# ATEMconsole.net
KiCad netlist of a schematic drawn in EAGLE
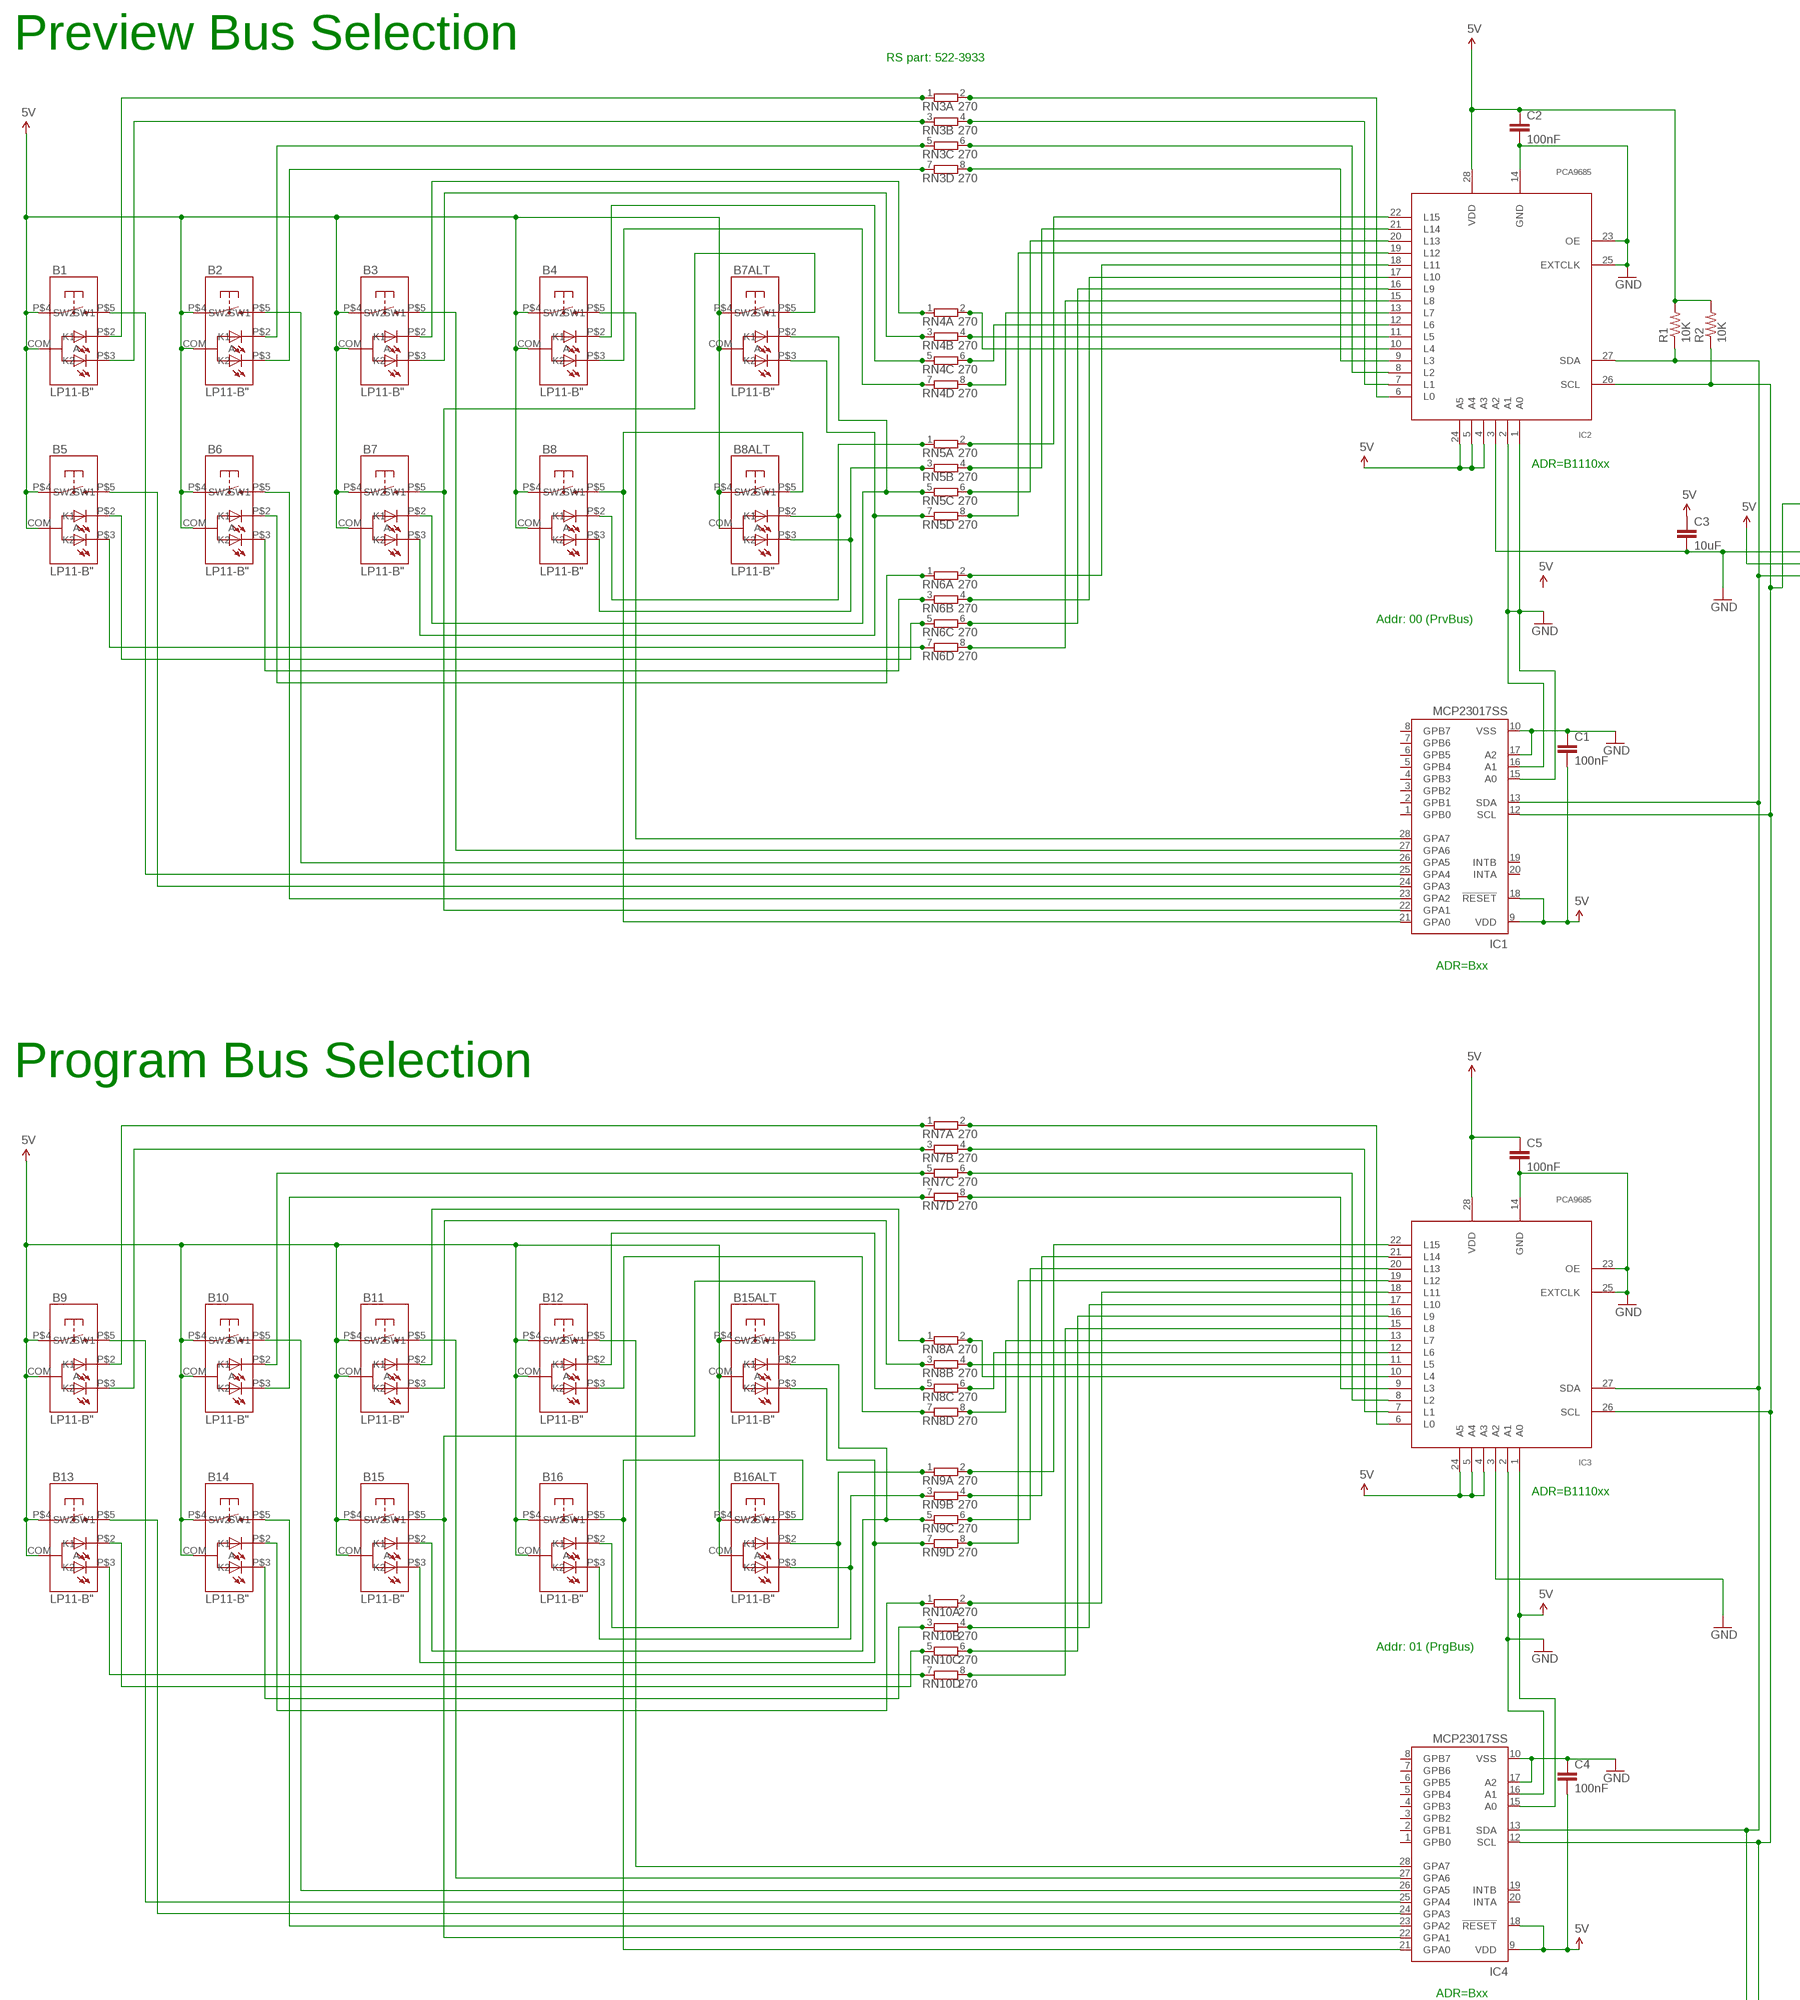
[diagram p0: schematic, sheet 1, part 1 of 3]
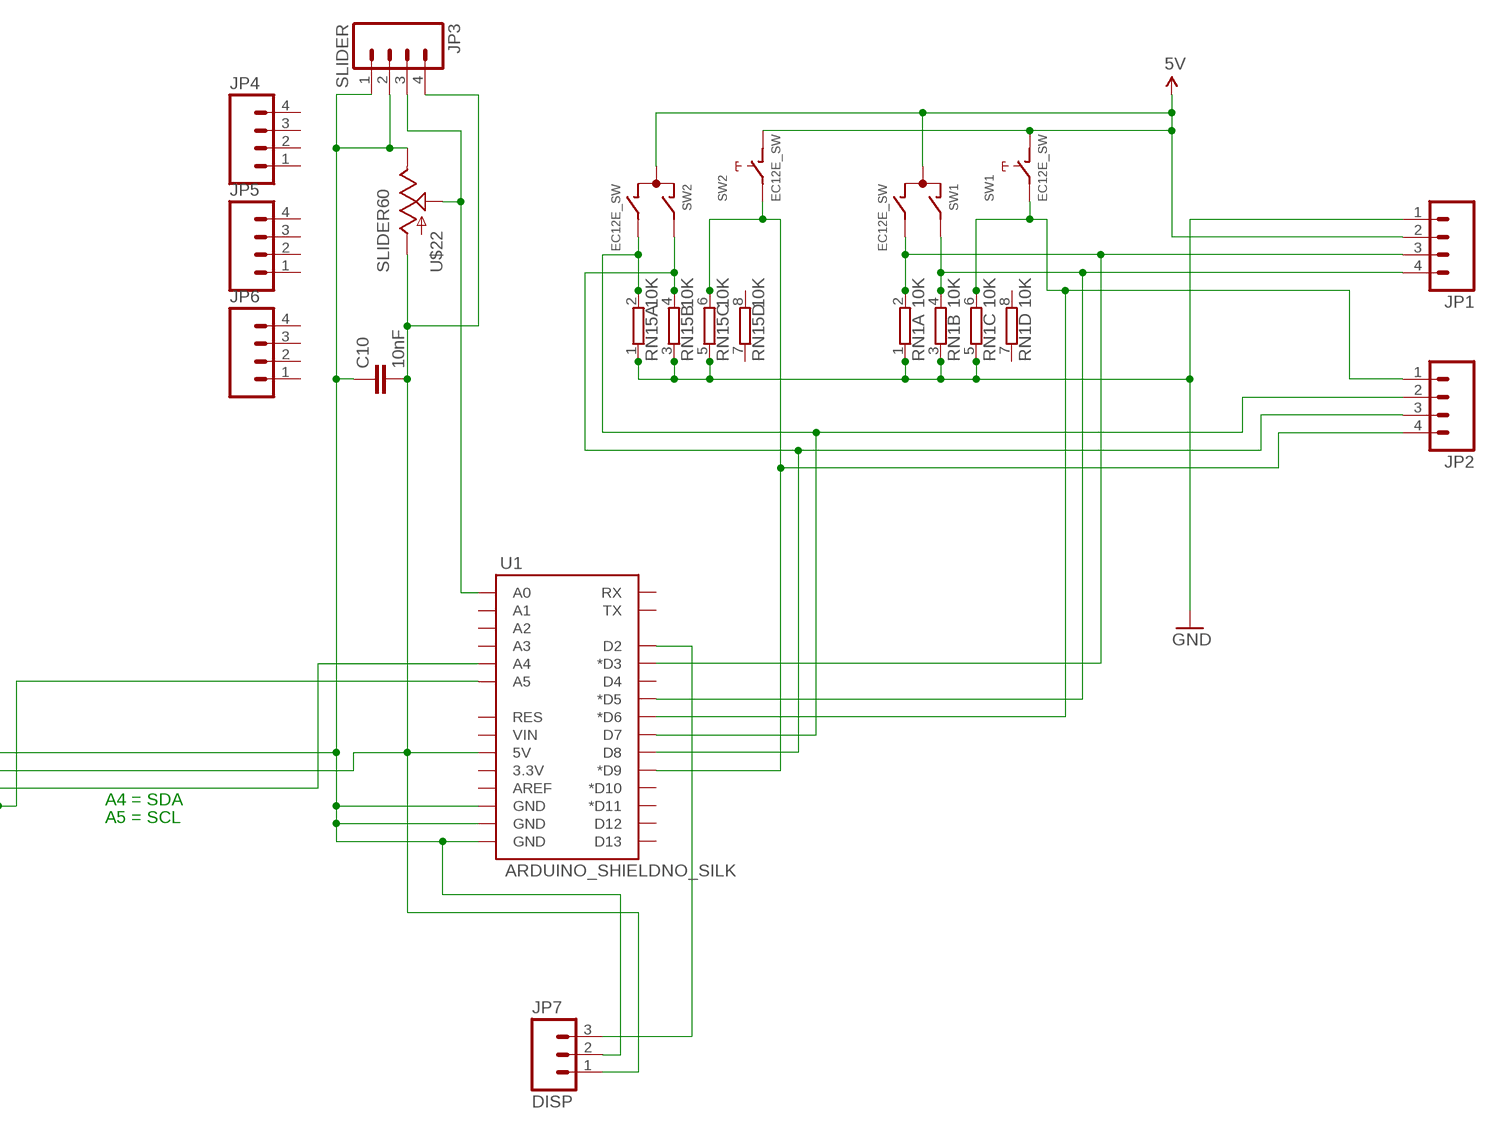
[diagram p1: schematic, sheet 1, part 2 of 3]
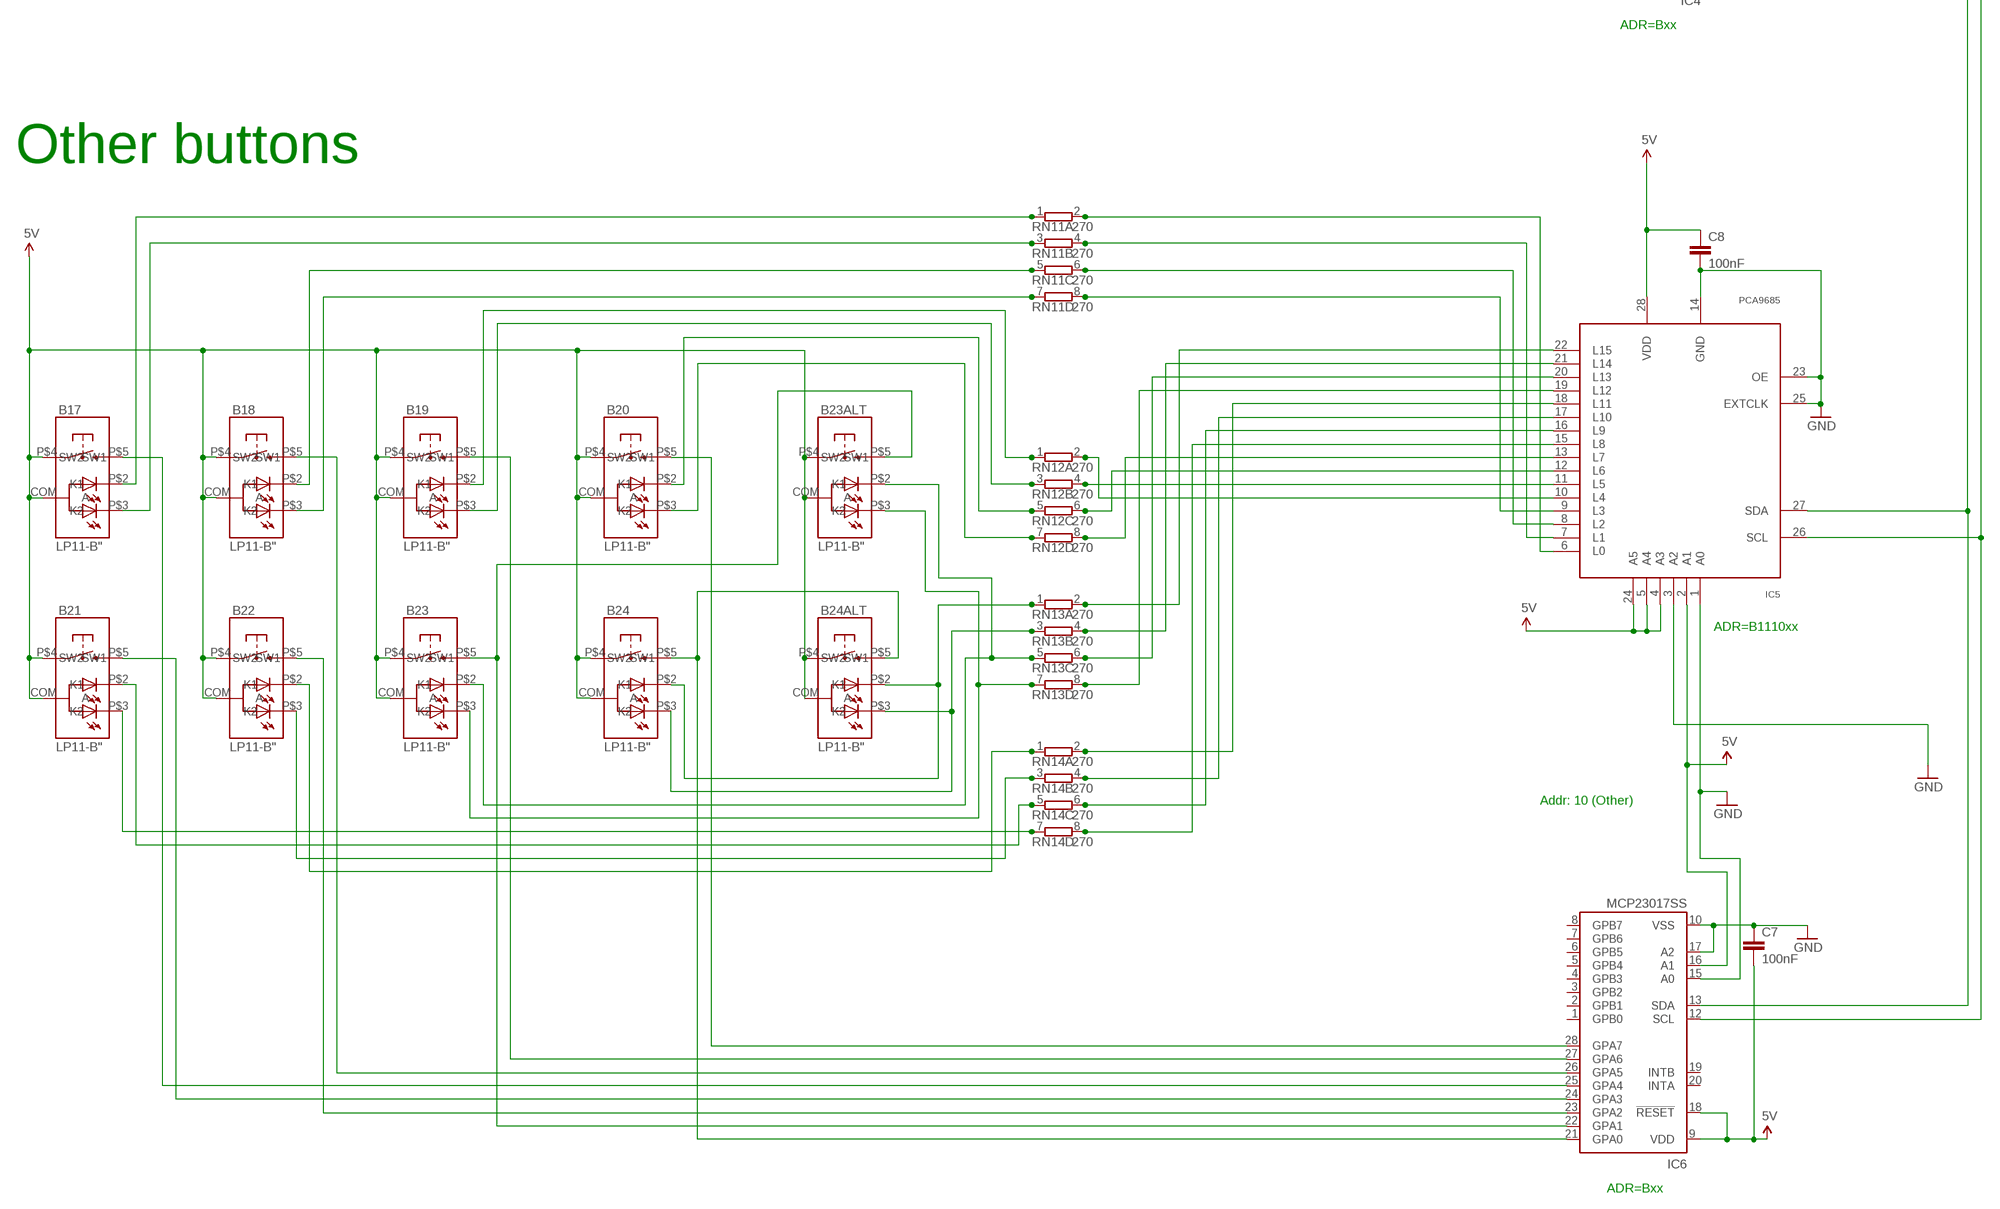
[diagram p2: schematic, sheet 1, part 3 of 3]

(export (version "E")
  (design (tool "Eeschema 10.0.6"))
  (components
    (comp (ref "B1")
      (value "LP11-B\"")
      (footprint "eagle-import:LP11")
      (libsource (lib "eagle-import") (part "LP11-B{dblquote}"))
    )
    (comp (ref "B2")
      (value "LP11-B\"")
      (footprint "eagle-import:LP11")
      (libsource (lib "eagle-import") (part "LP11-B{dblquote}"))
    )
    (comp (ref "B3")
      (value "LP11-B\"")
      (footprint "eagle-import:LP11")
      (libsource (lib "eagle-import") (part "LP11-B{dblquote}"))
    )
    (comp (ref "B4")
      (value "LP11-B\"")
      (footprint "eagle-import:LP11")
      (libsource (lib "eagle-import") (part "LP11-B{dblquote}"))
    )
    (comp (ref "B5")
      (value "LP11-B\"")
      (footprint "eagle-import:LP11")
      (libsource (lib "eagle-import") (part "LP11-B{dblquote}"))
    )
    (comp (ref "B6")
      (value "LP11-B\"")
      (footprint "eagle-import:LP11")
      (libsource (lib "eagle-import") (part "LP11-B{dblquote}"))
    )
    (comp (ref "B7")
      (value "LP11-B\"")
      (footprint "eagle-import:LP11")
      (libsource (lib "eagle-import") (part "LP11-B{dblquote}"))
    )
    (comp (ref "B7ALT")
      (value "LP11-B\"")
      (footprint "eagle-import:LP11")
      (libsource (lib "eagle-import") (part "LP11-B{dblquote}"))
    )
    (comp (ref "B8")
      (value "LP11-B\"")
      (footprint "eagle-import:LP11")
      (libsource (lib "eagle-import") (part "LP11-B{dblquote}"))
    )
    (comp (ref "B8ALT")
      (value "LP11-B\"")
      (footprint "eagle-import:LP11")
      (libsource (lib "eagle-import") (part "LP11-B{dblquote}"))
    )
    (comp (ref "B9")
      (value "LP11-B\"")
      (footprint "eagle-import:LP11")
      (libsource (lib "eagle-import") (part "LP11-B{dblquote}"))
    )
    (comp (ref "B10")
      (value "LP11-B\"")
      (footprint "eagle-import:LP11")
      (libsource (lib "eagle-import") (part "LP11-B{dblquote}"))
    )
    (comp (ref "B11")
      (value "LP11-B\"")
      (footprint "eagle-import:LP11")
      (libsource (lib "eagle-import") (part "LP11-B{dblquote}"))
    )
    (comp (ref "B12")
      (value "LP11-B\"")
      (footprint "eagle-import:LP11")
      (libsource (lib "eagle-import") (part "LP11-B{dblquote}"))
    )
    (comp (ref "B13")
      (value "LP11-B\"")
      (footprint "eagle-import:LP11")
      (libsource (lib "eagle-import") (part "LP11-B{dblquote}"))
    )
    (comp (ref "B14")
      (value "LP11-B\"")
      (footprint "eagle-import:LP11")
      (libsource (lib "eagle-import") (part "LP11-B{dblquote}"))
    )
    (comp (ref "B15")
      (value "LP11-B\"")
      (footprint "eagle-import:LP11")
      (libsource (lib "eagle-import") (part "LP11-B{dblquote}"))
    )
    (comp (ref "B15ALT")
      (value "LP11-B\"")
      (footprint "eagle-import:LP11")
      (libsource (lib "eagle-import") (part "LP11-B{dblquote}"))
    )
    (comp (ref "B16")
      (value "LP11-B\"")
      (footprint "eagle-import:LP11")
      (libsource (lib "eagle-import") (part "LP11-B{dblquote}"))
    )
    (comp (ref "B16ALT")
      (value "LP11-B\"")
      (footprint "eagle-import:LP11")
      (libsource (lib "eagle-import") (part "LP11-B{dblquote}"))
    )
    (comp (ref "B17")
      (value "LP11-B\"")
      (footprint "eagle-import:LP11")
      (libsource (lib "eagle-import") (part "LP11-B{dblquote}"))
    )
    (comp (ref "B18")
      (value "LP11-B\"")
      (footprint "eagle-import:LP11")
      (libsource (lib "eagle-import") (part "LP11-B{dblquote}"))
    )
    (comp (ref "B19")
      (value "LP11-B\"")
      (footprint "eagle-import:LP11")
      (libsource (lib "eagle-import") (part "LP11-B{dblquote}"))
    )
    (comp (ref "B20")
      (value "LP11-B\"")
      (footprint "eagle-import:LP11")
      (libsource (lib "eagle-import") (part "LP11-B{dblquote}"))
    )
    (comp (ref "B21")
      (value "LP11-B\"")
      (footprint "eagle-import:LP11")
      (libsource (lib "eagle-import") (part "LP11-B{dblquote}"))
    )
    (comp (ref "B22")
      (value "LP11-B\"")
      (footprint "eagle-import:LP11")
      (libsource (lib "eagle-import") (part "LP11-B{dblquote}"))
    )
    (comp (ref "B23")
      (value "LP11-B\"")
      (footprint "eagle-import:LP11")
      (libsource (lib "eagle-import") (part "LP11-B{dblquote}"))
    )
    (comp (ref "B23ALT")
      (value "LP11-B\"")
      (footprint "eagle-import:LP11")
      (libsource (lib "eagle-import") (part "LP11-B{dblquote}"))
    )
    (comp (ref "B24")
      (value "LP11-B\"")
      (footprint "eagle-import:LP11")
      (libsource (lib "eagle-import") (part "LP11-B{dblquote}"))
    )
    (comp (ref "B24ALT")
      (value "LP11-B\"")
      (footprint "eagle-import:LP11")
      (libsource (lib "eagle-import") (part "LP11-B{dblquote}"))
    )
    (comp (ref "C1")
      (value "100nF")
      (footprint "eagle-import:AXIAL-5MM")
      (libsource (lib "eagle-import") (part "CAP_"))
    )
    (comp (ref "C2")
      (value "100nF")
      (footprint "eagle-import:AXIAL-5MM")
      (libsource (lib "eagle-import") (part "CAP_"))
    )
    (comp (ref "C3")
      (value "10uF")
      (footprint "eagle-import:AXIAL-5MM")
      (libsource (lib "eagle-import") (part "CAP_"))
    )
    (comp (ref "C4")
      (value "100nF")
      (footprint "eagle-import:AXIAL-5MM")
      (libsource (lib "eagle-import") (part "CAP_"))
    )
    (comp (ref "C5")
      (value "100nF")
      (footprint "eagle-import:AXIAL-5MM")
      (libsource (lib "eagle-import") (part "CAP_"))
    )
    (comp (ref "C7")
      (value "100nF")
      (footprint "eagle-import:AXIAL-5MM")
      (libsource (lib "eagle-import") (part "CAP_"))
    )
    (comp (ref "C8")
      (value "100nF")
      (footprint "eagle-import:AXIAL-5MM")
      (libsource (lib "eagle-import") (part "CAP_"))
    )
    (comp (ref "C10")
      (value "10nF")
      (footprint "eagle-import:AXIAL-5MM")
      (libsource (lib "eagle-import") (part "CAP_"))
    )
    (comp (ref "IC1")
      (value "MCP23017SS")
      (footprint "eagle-import:SSOP28")
      (fields
        (field (name "MF") "MICROCHIP")
        (field (name "MPN") "MCP23017-E/SS")
        (field (name "MPN_1") "MCP23017-E/SS")
        (field (name "OC_FARNELL") "1467674")
        (field (name "OC_NEWARK") "31K2960")
      )
      (libsource (lib "eagle-import") (part "MCP23017SS"))
    )
    (comp (ref "IC2")
      (value "PCA9685")
      (footprint "eagle-import:TSSOP28")
      (libsource (lib "eagle-import") (part "PCA9685"))
    )
    (comp (ref "IC3")
      (value "PCA9685")
      (footprint "eagle-import:TSSOP28")
      (libsource (lib "eagle-import") (part "PCA9685"))
    )
    (comp (ref "IC4")
      (value "MCP23017SS")
      (footprint "eagle-import:SSOP28")
      (fields
        (field (name "MF") "MICROCHIP")
        (field (name "MPN") "MCP23017-E/SS")
        (field (name "MPN_1") "MCP23017-E/SS")
        (field (name "OC_FARNELL") "1467674")
        (field (name "OC_NEWARK") "31K2960")
      )
      (libsource (lib "eagle-import") (part "MCP23017SS"))
    )
    (comp (ref "IC5")
      (value "PCA9685")
      (footprint "eagle-import:TSSOP28")
      (libsource (lib "eagle-import") (part "PCA9685"))
    )
    (comp (ref "IC6")
      (value "MCP23017SS")
      (footprint "eagle-import:SSOP28")
      (fields
        (field (name "MF") "MICROCHIP")
        (field (name "MPN") "MCP23017-E/SS")
        (field (name "MPN_1") "MCP23017-E/SS")
        (field (name "OC_FARNELL") "1467674")
        (field (name "OC_NEWARK") "31K2960")
      )
      (libsource (lib "eagle-import") (part "MCP23017SS"))
    )
    (comp (ref "JP1")
      (value "M04PTH")
      (footprint "eagle-import:1X04")
      (libsource (lib "eagle-import") (part "M04PTH"))
    )
    (comp (ref "JP2")
      (value "M04PTH")
      (footprint "eagle-import:1X04")
      (libsource (lib "eagle-import") (part "M04PTH"))
    )
    (comp (ref "JP3")
      (value "SLIDER")
      (footprint "eagle-import:1X04")
      (libsource (lib "eagle-import") (part "M04PTH"))
    )
    (comp (ref "JP4")
      (value "M04PTH")
      (footprint "eagle-import:1X04")
      (libsource (lib "eagle-import") (part "M04PTH"))
    )
    (comp (ref "JP5")
      (value "M04PTH")
      (footprint "eagle-import:1X04")
      (libsource (lib "eagle-import") (part "M04PTH"))
    )
    (comp (ref "JP6")
      (value "M04PTH")
      (footprint "eagle-import:1X04")
      (libsource (lib "eagle-import") (part "M04PTH"))
    )
    (comp (ref "JP7")
      (value "DISP")
      (footprint "eagle-import:1X03")
      (libsource (lib "eagle-import") (part "M03PTH"))
    )
    (comp (ref "R1")
      (value "10K")
      (footprint "eagle-import:0603-RES")
      (libsource (lib "eagle-import") (part "RESISTOR0603-RES"))
    )
    (comp (ref "R2")
      (value "10K")
      (footprint "eagle-import:0603-RES")
      (libsource (lib "eagle-import") (part "RESISTOR0603-RES"))
    )
    (comp (ref "RN1")
      (value "10K")
      (footprint "eagle-import:SIL8")
      (libsource (lib "eagle-import") (part "E4R"))
    )
    (comp (ref "RN3")
      (value "270")
      (footprint "eagle-import:SIL8")
      (libsource (lib "eagle-import") (part "E4R"))
    )
    (comp (ref "RN4")
      (value "270")
      (footprint "eagle-import:SIL8")
      (libsource (lib "eagle-import") (part "E4R"))
    )
    (comp (ref "RN5")
      (value "270")
      (footprint "eagle-import:SIL8")
      (libsource (lib "eagle-import") (part "E4R"))
    )
    (comp (ref "RN6")
      (value "270")
      (footprint "eagle-import:SIL8")
      (libsource (lib "eagle-import") (part "E4R"))
    )
    (comp (ref "RN7")
      (value "270")
      (footprint "eagle-import:SIL8")
      (libsource (lib "eagle-import") (part "E4R"))
    )
    (comp (ref "RN8")
      (value "270")
      (footprint "eagle-import:SIL8")
      (libsource (lib "eagle-import") (part "E4R"))
    )
    (comp (ref "RN9")
      (value "270")
      (footprint "eagle-import:SIL8")
      (libsource (lib "eagle-import") (part "E4R"))
    )
    (comp (ref "RN10")
      (value "270")
      (footprint "eagle-import:SIL8")
      (libsource (lib "eagle-import") (part "E4R"))
    )
    (comp (ref "RN11")
      (value "270")
      (footprint "eagle-import:SIL8")
      (libsource (lib "eagle-import") (part "E4R"))
    )
    (comp (ref "RN12")
      (value "270")
      (footprint "eagle-import:SIL8")
      (libsource (lib "eagle-import") (part "E4R"))
    )
    (comp (ref "RN13")
      (value "270")
      (footprint "eagle-import:SIL8")
      (libsource (lib "eagle-import") (part "E4R"))
    )
    (comp (ref "RN14")
      (value "270")
      (footprint "eagle-import:SIL8")
      (libsource (lib "eagle-import") (part "E4R"))
    )
    (comp (ref "RN15")
      (value "10K")
      (footprint "eagle-import:SIL8")
      (libsource (lib "eagle-import") (part "E4R"))
    )
    (comp (ref "SW1")
      (value "EC12E_SW")
      (footprint "eagle-import:ALPS_EC12E_SW")
      (fields (field (name "MPN") "EC12E2424407"))
      (libsource (lib "eagle-import") (part "EC12E_SW"))
    )
    (comp (ref "SW2")
      (value "EC12E_SW")
      (footprint "eagle-import:ALPS_EC12E_SW")
      (fields (field (name "MPN") "EC12E2424407"))
      (libsource (lib "eagle-import") (part "EC12E_SW"))
    )
    (comp (ref "U$22")
      (value "SLIDER60")
      (footprint "eagle-import:SLIDER60")
      (libsource (lib "eagle-import") (part "SLIDER60"))
    )
    (comp (ref "U1")
      (value "ARDUINO_SHIELDNO_SILK")
      (footprint "eagle-import:DUEMILANOVE_VIAS")
      (libsource (lib "eagle-import") (part "ARDUINO_SHIELDNO_SILK"))
    )
  )
  (nets
    (net (code "1") (name "5V") (class "Default")
      (node (ref "B1") (pin "COM") (pinfunction "A_COM") (pintype "bidirectional"))
      (node (ref "B1") (pin "P$4") (pinfunction "SW1_P$4") (pintype "bidirectional"))
      (node (ref "B10") (pin "COM") (pinfunction "A_COM") (pintype "bidirectional"))
      (node (ref "B10") (pin "P$4") (pinfunction "SW1_P$4") (pintype "bidirectional"))
      (node (ref "B11") (pin "COM") (pinfunction "A_COM") (pintype "bidirectional"))
      (node (ref "B11") (pin "P$4") (pinfunction "SW1_P$4") (pintype "bidirectional"))
      (node (ref "B12") (pin "COM") (pinfunction "A_COM") (pintype "bidirectional"))
      (node (ref "B12") (pin "P$4") (pinfunction "SW1_P$4") (pintype "bidirectional"))
      (node (ref "B13") (pin "COM") (pinfunction "A_COM") (pintype "bidirectional"))
      (node (ref "B13") (pin "P$4") (pinfunction "SW1_P$4") (pintype "bidirectional"))
      (node (ref "B14") (pin "COM") (pinfunction "A_COM") (pintype "bidirectional"))
      (node (ref "B14") (pin "P$4") (pinfunction "SW1_P$4") (pintype "bidirectional"))
      (node (ref "B15") (pin "COM") (pinfunction "A_COM") (pintype "bidirectional"))
      (node (ref "B15") (pin "P$4") (pinfunction "SW1_P$4") (pintype "bidirectional"))
      (node (ref "B15ALT") (pin "COM") (pinfunction "A_COM") (pintype "bidirectional"))
      (node (ref "B15ALT") (pin "P$4") (pinfunction "SW1_P$4") (pintype "bidirectional"))
      (node (ref "B16") (pin "COM") (pinfunction "A_COM") (pintype "bidirectional"))
      (node (ref "B16") (pin "P$4") (pinfunction "SW1_P$4") (pintype "bidirectional"))
      (node (ref "B16ALT") (pin "COM") (pinfunction "A_COM") (pintype "bidirectional"))
      (node (ref "B16ALT") (pin "P$4") (pinfunction "SW1_P$4") (pintype "bidirectional"))
      (node (ref "B17") (pin "COM") (pinfunction "A_COM") (pintype "bidirectional"))
      (node (ref "B17") (pin "P$4") (pinfunction "SW1_P$4") (pintype "bidirectional"))
      (node (ref "B18") (pin "COM") (pinfunction "A_COM") (pintype "bidirectional"))
      (node (ref "B18") (pin "P$4") (pinfunction "SW1_P$4") (pintype "bidirectional"))
      (node (ref "B19") (pin "COM") (pinfunction "A_COM") (pintype "bidirectional"))
      (node (ref "B19") (pin "P$4") (pinfunction "SW1_P$4") (pintype "bidirectional"))
      (node (ref "B2") (pin "COM") (pinfunction "A_COM") (pintype "bidirectional"))
      (node (ref "B2") (pin "P$4") (pinfunction "SW1_P$4") (pintype "bidirectional"))
      (node (ref "B20") (pin "COM") (pinfunction "A_COM") (pintype "bidirectional"))
      (node (ref "B20") (pin "P$4") (pinfunction "SW1_P$4") (pintype "bidirectional"))
      (node (ref "B21") (pin "COM") (pinfunction "A_COM") (pintype "bidirectional"))
      (node (ref "B21") (pin "P$4") (pinfunction "SW1_P$4") (pintype "bidirectional"))
      (node (ref "B22") (pin "COM") (pinfunction "A_COM") (pintype "bidirectional"))
      (node (ref "B22") (pin "P$4") (pinfunction "SW1_P$4") (pintype "bidirectional"))
      (node (ref "B23") (pin "COM") (pinfunction "A_COM") (pintype "bidirectional"))
      (node (ref "B23") (pin "P$4") (pinfunction "SW1_P$4") (pintype "bidirectional"))
      (node (ref "B23ALT") (pin "COM") (pinfunction "A_COM") (pintype "bidirectional"))
      (node (ref "B23ALT") (pin "P$4") (pinfunction "SW1_P$4") (pintype "bidirectional"))
      (node (ref "B24") (pin "COM") (pinfunction "A_COM") (pintype "bidirectional"))
      (node (ref "B24") (pin "P$4") (pinfunction "SW1_P$4") (pintype "bidirectional"))
      (node (ref "B24ALT") (pin "COM") (pinfunction "A_COM") (pintype "bidirectional"))
      (node (ref "B24ALT") (pin "P$4") (pinfunction "SW1_P$4") (pintype "bidirectional"))
      (node (ref "B3") (pin "COM") (pinfunction "A_COM") (pintype "bidirectional"))
      (node (ref "B3") (pin "P$4") (pinfunction "SW1_P$4") (pintype "bidirectional"))
      (node (ref "B4") (pin "COM") (pinfunction "A_COM") (pintype "bidirectional"))
      (node (ref "B4") (pin "P$4") (pinfunction "SW1_P$4") (pintype "bidirectional"))
      (node (ref "B5") (pin "COM") (pinfunction "A_COM") (pintype "bidirectional"))
      (node (ref "B5") (pin "P$4") (pinfunction "SW1_P$4") (pintype "bidirectional"))
      (node (ref "B6") (pin "COM") (pinfunction "A_COM") (pintype "bidirectional"))
      (node (ref "B6") (pin "P$4") (pinfunction "SW1_P$4") (pintype "bidirectional"))
      (node (ref "B7") (pin "COM") (pinfunction "A_COM") (pintype "bidirectional"))
      (node (ref "B7") (pin "P$4") (pinfunction "SW1_P$4") (pintype "bidirectional"))
      (node (ref "B7ALT") (pin "COM") (pinfunction "A_COM") (pintype "bidirectional"))
      (node (ref "B7ALT") (pin "P$4") (pinfunction "SW1_P$4") (pintype "bidirectional"))
      (node (ref "B8") (pin "COM") (pinfunction "A_COM") (pintype "bidirectional"))
      (node (ref "B8") (pin "P$4") (pinfunction "SW1_P$4") (pintype "bidirectional"))
      (node (ref "B8ALT") (pin "COM") (pinfunction "A_COM") (pintype "bidirectional"))
      (node (ref "B8ALT") (pin "P$4") (pinfunction "SW1_P$4") (pintype "bidirectional"))
      (node (ref "B9") (pin "COM") (pinfunction "A_COM") (pintype "bidirectional"))
      (node (ref "B9") (pin "P$4") (pinfunction "SW1_P$4") (pintype "bidirectional"))
      (node (ref "C1") (pin "P$2") (pinfunction "2_P$2") (pintype "passive"))
      (node (ref "C10") (pin "P$2") (pinfunction "2_P$2") (pintype "passive"))
      (node (ref "C2") (pin "P$1") (pinfunction "1_P$1") (pintype "passive"))
      (node (ref "C3") (pin "P$1") (pinfunction "1_P$1") (pintype "passive"))
      (node (ref "C4") (pin "P$2") (pinfunction "2_P$2") (pintype "passive"))
      (node (ref "C5") (pin "P$1") (pinfunction "1_P$1") (pintype "passive"))
      (node (ref "C7") (pin "P$2") (pinfunction "2_P$2") (pintype "passive"))
      (node (ref "C8") (pin "P$1") (pinfunction "1_P$1") (pintype "passive"))
      (node (ref "IC1") (pin "18") (pinfunction "~{RESET}_18") (pintype "input"))
      (node (ref "IC1") (pin "9") (pinfunction "VDD_9") (pintype "power_in"))
      (node (ref "IC2") (pin "24") (pinfunction "A5_24") (pintype "input"))
      (node (ref "IC2") (pin "28") (pinfunction "VDD_28") (pintype "power_in"))
      (node (ref "IC2") (pin "4") (pinfunction "A3_4") (pintype "input"))
      (node (ref "IC2") (pin "5") (pinfunction "A4_5") (pintype "input"))
      (node (ref "IC3") (pin "1") (pinfunction "A0_1") (pintype "input"))
      (node (ref "IC3") (pin "24") (pinfunction "A5_24") (pintype "input"))
      (node (ref "IC3") (pin "28") (pinfunction "VDD_28") (pintype "power_in"))
      (node (ref "IC3") (pin "4") (pinfunction "A3_4") (pintype "input"))
      (node (ref "IC3") (pin "5") (pinfunction "A4_5") (pintype "input"))
      (node (ref "IC4") (pin "15") (pinfunction "A0_15") (pintype "input"))
      (node (ref "IC4") (pin "18") (pinfunction "~{RESET}_18") (pintype "input"))
      (node (ref "IC4") (pin "9") (pinfunction "VDD_9") (pintype "power_in"))
      (node (ref "IC5") (pin "2") (pinfunction "A1_2") (pintype "input"))
      (node (ref "IC5") (pin "24") (pinfunction "A5_24") (pintype "input"))
      (node (ref "IC5") (pin "28") (pinfunction "VDD_28") (pintype "power_in"))
      (node (ref "IC5") (pin "4") (pinfunction "A3_4") (pintype "input"))
      (node (ref "IC5") (pin "5") (pinfunction "A4_5") (pintype "input"))
      (node (ref "IC6") (pin "16") (pinfunction "A1_16") (pintype "input"))
      (node (ref "IC6") (pin "18") (pinfunction "~{RESET}_18") (pintype "input"))
      (node (ref "IC6") (pin "9") (pinfunction "VDD_9") (pintype "power_in"))
      (node (ref "JP1") (pin "2") (pinfunction "2_2") (pintype "passive"))
      (node (ref "JP3") (pin "4") (pinfunction "4_4") (pintype "passive"))
      (node (ref "JP7") (pin "1") (pinfunction "1_1") (pintype "passive"))
      (node (ref "R1") (pin "2") (pinfunction "2_2") (pintype "passive"))
      (node (ref "R2") (pin "2") (pinfunction "2_2") (pintype "passive"))
      (node (ref "SW1") (pin "C") (pinfunction "C_C") (pintype "passive"))
      (node (ref "SW1") (pin "D") (pinfunction "1_D") (pintype "passive"))
      (node (ref "SW2") (pin "C") (pinfunction "C_C") (pintype "passive"))
      (node (ref "SW2") (pin "D") (pinfunction "1_D") (pintype "passive"))
      (node (ref "U$22") (pin "3") (pinfunction "A_3") (pintype "passive"))
      (node (ref "U1") (pin "5V") (pinfunction "5V_5V") (pintype "bidirectional"))
    )
    (net (code "2") (name "GND") (class "Default")
      (node (ref "C1") (pin "P$1") (pinfunction "1_P$1") (pintype "passive"))
      (node (ref "C10") (pin "P$1") (pinfunction "1_P$1") (pintype "passive"))
      (node (ref "C2") (pin "P$2") (pinfunction "2_P$2") (pintype "passive"))
      (node (ref "C3") (pin "P$2") (pinfunction "2_P$2") (pintype "passive"))
      (node (ref "C4") (pin "P$1") (pinfunction "1_P$1") (pintype "passive"))
      (node (ref "C5") (pin "P$2") (pinfunction "2_P$2") (pintype "passive"))
      (node (ref "C7") (pin "P$1") (pinfunction "1_P$1") (pintype "passive"))
      (node (ref "C8") (pin "P$2") (pinfunction "2_P$2") (pintype "passive"))
      (node (ref "IC1") (pin "10") (pinfunction "VSS_10") (pintype "power_in"))
      (node (ref "IC1") (pin "15") (pinfunction "A0_15") (pintype "input"))
      (node (ref "IC1") (pin "16") (pinfunction "A1_16") (pintype "input"))
      (node (ref "IC1") (pin "17") (pinfunction "A2_17") (pintype "input"))
      (node (ref "IC2") (pin "1") (pinfunction "A0_1") (pintype "input"))
      (node (ref "IC2") (pin "14") (pinfunction "GND_14") (pintype "power_in"))
      (node (ref "IC2") (pin "2") (pinfunction "A1_2") (pintype "input"))
      (node (ref "IC2") (pin "23") (pinfunction "OE_23") (pintype "input"))
      (node (ref "IC2") (pin "25") (pinfunction "EXTCLK_25") (pintype "input"))
      (node (ref "IC2") (pin "3") (pinfunction "A2_3") (pintype "input"))
      (node (ref "IC3") (pin "14") (pinfunction "GND_14") (pintype "power_in"))
      (node (ref "IC3") (pin "2") (pinfunction "A1_2") (pintype "input"))
      (node (ref "IC3") (pin "23") (pinfunction "OE_23") (pintype "input"))
      (node (ref "IC3") (pin "25") (pinfunction "EXTCLK_25") (pintype "input"))
      (node (ref "IC3") (pin "3") (pinfunction "A2_3") (pintype "input"))
      (node (ref "IC4") (pin "10") (pinfunction "VSS_10") (pintype "power_in"))
      (node (ref "IC4") (pin "16") (pinfunction "A1_16") (pintype "input"))
      (node (ref "IC4") (pin "17") (pinfunction "A2_17") (pintype "input"))
      (node (ref "IC5") (pin "1") (pinfunction "A0_1") (pintype "input"))
      (node (ref "IC5") (pin "14") (pinfunction "GND_14") (pintype "power_in"))
      (node (ref "IC5") (pin "23") (pinfunction "OE_23") (pintype "input"))
      (node (ref "IC5") (pin "25") (pinfunction "EXTCLK_25") (pintype "input"))
      (node (ref "IC5") (pin "3") (pinfunction "A2_3") (pintype "input"))
      (node (ref "IC6") (pin "10") (pinfunction "VSS_10") (pintype "power_in"))
      (node (ref "IC6") (pin "15") (pinfunction "A0_15") (pintype "input"))
      (node (ref "IC6") (pin "17") (pinfunction "A2_17") (pintype "input"))
      (node (ref "JP1") (pin "1") (pinfunction "1_1") (pintype "passive"))
      (node (ref "JP3") (pin "1") (pinfunction "1_1") (pintype "passive"))
      (node (ref "JP3") (pin "2") (pinfunction "2_2") (pintype "passive"))
      (node (ref "JP7") (pin "2") (pinfunction "2_2") (pintype "passive"))
      (node (ref "RN1") (pin "1") (pinfunction "1_1") (pintype "passive"))
      (node (ref "RN1") (pin "3") (pinfunction "1_3") (pintype "passive"))
      (node (ref "RN1") (pin "5") (pinfunction "1_5") (pintype "passive"))
      (node (ref "RN15") (pin "1") (pinfunction "1_1") (pintype "passive"))
      (node (ref "RN15") (pin "3") (pinfunction "1_3") (pintype "passive"))
      (node (ref "RN15") (pin "5") (pinfunction "1_5") (pintype "passive"))
      (node (ref "U$22") (pin "1") (pinfunction "E_1") (pintype "passive"))
      (node (ref "U1") (pin "GND@0") (pinfunction "GND_GND@0") (pintype "bidirectional"))
      (node (ref "U1") (pin "GND@1") (pinfunction "GND_GND@1") (pintype "bidirectional"))
      (node (ref "U1") (pin "GND@2") (pinfunction "GND_GND@2") (pintype "bidirectional"))
    )
    (net (code "3") (name "Net-(B1-K1)") (class "Default")
      (node (ref "B1") (pin "P$2") (pinfunction "K1_P$2") (pintype "bidirectional"))
      (node (ref "RN3") (pin "1") (pinfunction "1_1") (pintype "passive"))
    )
    (net (code "4") (name "Net-(B1-K2)") (class "Default")
      (node (ref "B1") (pin "P$3") (pinfunction "K2_P$3") (pintype "bidirectional"))
      (node (ref "RN3") (pin "3") (pinfunction "1_3") (pintype "passive"))
    )
    (net (code "5") (name "Net-(B1-SW2)") (class "Default")
      (node (ref "B1") (pin "P$5") (pinfunction "SW2_P$5") (pintype "bidirectional"))
      (node (ref "IC1") (pin "25") (pinfunction "GPA4_25") (pintype "bidirectional"))
    )
    (net (code "6") (name "Net-(B2-K1)") (class "Default")
      (node (ref "B2") (pin "P$2") (pinfunction "K1_P$2") (pintype "bidirectional"))
      (node (ref "RN3") (pin "5") (pinfunction "1_5") (pintype "passive"))
    )
    (net (code "7") (name "Net-(B2-K2)") (class "Default")
      (node (ref "B2") (pin "P$3") (pinfunction "K2_P$3") (pintype "bidirectional"))
      (node (ref "RN3") (pin "7") (pinfunction "1_7") (pintype "passive"))
    )
    (net (code "8") (name "Net-(B2-SW2)") (class "Default")
      (node (ref "B2") (pin "P$5") (pinfunction "SW2_P$5") (pintype "bidirectional"))
      (node (ref "IC1") (pin "26") (pinfunction "GPA5_26") (pintype "bidirectional"))
    )
    (net (code "9") (name "Net-(B3-K1)") (class "Default")
      (node (ref "B3") (pin "P$2") (pinfunction "K1_P$2") (pintype "bidirectional"))
      (node (ref "RN4") (pin "1") (pinfunction "1_1") (pintype "passive"))
    )
    (net (code "10") (name "Net-(B3-K2)") (class "Default")
      (node (ref "B3") (pin "P$3") (pinfunction "K2_P$3") (pintype "bidirectional"))
      (node (ref "RN4") (pin "3") (pinfunction "1_3") (pintype "passive"))
    )
    (net (code "11") (name "Net-(B3-SW2)") (class "Default")
      (node (ref "B3") (pin "P$5") (pinfunction "SW2_P$5") (pintype "bidirectional"))
      (node (ref "IC1") (pin "27") (pinfunction "GPA6_27") (pintype "bidirectional"))
    )
    (net (code "12") (name "Net-(B4-K1)") (class "Default")
      (node (ref "B4") (pin "P$2") (pinfunction "K1_P$2") (pintype "bidirectional"))
      (node (ref "RN4") (pin "5") (pinfunction "1_5") (pintype "passive"))
    )
    (net (code "13") (name "Net-(B4-K2)") (class "Default")
      (node (ref "B4") (pin "P$3") (pinfunction "K2_P$3") (pintype "bidirectional"))
      (node (ref "RN4") (pin "7") (pinfunction "1_7") (pintype "passive"))
    )
    (net (code "14") (name "Net-(B4-SW2)") (class "Default")
      (node (ref "B4") (pin "P$5") (pinfunction "SW2_P$5") (pintype "bidirectional"))
      (node (ref "IC1") (pin "28") (pinfunction "GPA7_28") (pintype "bidirectional"))
    )
    (net (code "15") (name "Net-(B5-K1)") (class "Default")
      (node (ref "B5") (pin "P$2") (pinfunction "K1_P$2") (pintype "bidirectional"))
      (node (ref "RN6") (pin "5") (pinfunction "1_5") (pintype "passive"))
    )
    (net (code "16") (name "Net-(B5-K2)") (class "Default")
      (node (ref "B5") (pin "P$3") (pinfunction "K2_P$3") (pintype "bidirectional"))
      (node (ref "RN6") (pin "7") (pinfunction "1_7") (pintype "passive"))
    )
    (net (code "17") (name "Net-(B5-SW2)") (class "Default")
      (node (ref "B5") (pin "P$5") (pinfunction "SW2_P$5") (pintype "bidirectional"))
      (node (ref "IC1") (pin "24") (pinfunction "GPA3_24") (pintype "bidirectional"))
    )
    (net (code "18") (name "Net-(B6-K1)") (class "Default")
      (node (ref "B6") (pin "P$2") (pinfunction "K1_P$2") (pintype "bidirectional"))
      (node (ref "RN6") (pin "1") (pinfunction "1_1") (pintype "passive"))
    )
    (net (code "19") (name "Net-(B6-K2)") (class "Default")
      (node (ref "B6") (pin "P$3") (pinfunction "K2_P$3") (pintype "bidirectional"))
      (node (ref "RN6") (pin "3") (pinfunction "1_3") (pintype "passive"))
    )
    (net (code "20") (name "Net-(B6-SW2)") (class "Default")
      (node (ref "B6") (pin "P$5") (pinfunction "SW2_P$5") (pintype "bidirectional"))
      (node (ref "IC1") (pin "23") (pinfunction "GPA2_23") (pintype "bidirectional"))
    )
    (net (code "21") (name "Net-(B7-K1)") (class "Default")
      (node (ref "B7") (pin "P$2") (pinfunction "K1_P$2") (pintype "bidirectional"))
      (node (ref "B7ALT") (pin "P$2") (pinfunction "K1_P$2") (pintype "bidirectional"))
      (node (ref "RN5") (pin "5") (pinfunction "1_5") (pintype "passive"))
    )
    (net (code "22") (name "Net-(B7-K2)") (class "Default")
      (node (ref "B7") (pin "P$3") (pinfunction "K2_P$3") (pintype "bidirectional"))
      (node (ref "B7ALT") (pin "P$3") (pinfunction "K2_P$3") (pintype "bidirectional"))
      (node (ref "RN5") (pin "7") (pinfunction "1_7") (pintype "passive"))
    )
    (net (code "23") (name "Net-(B7-SW2)") (class "Default")
      (node (ref "B7") (pin "P$5") (pinfunction "SW2_P$5") (pintype "bidirectional"))
      (node (ref "B7ALT") (pin "P$5") (pinfunction "SW2_P$5") (pintype "bidirectional"))
      (node (ref "IC1") (pin "22") (pinfunction "GPA1_22") (pintype "bidirectional"))
    )
    (net (code "24") (name "Net-(B8-K1)") (class "Default")
      (node (ref "B8") (pin "P$2") (pinfunction "K1_P$2") (pintype "bidirectional"))
      (node (ref "B8ALT") (pin "P$2") (pinfunction "K1_P$2") (pintype "bidirectional"))
      (node (ref "RN5") (pin "1") (pinfunction "1_1") (pintype "passive"))
    )
    (net (code "25") (name "Net-(B8-K2)") (class "Default")
      (node (ref "B8") (pin "P$3") (pinfunction "K2_P$3") (pintype "bidirectional"))
      (node (ref "B8ALT") (pin "P$3") (pinfunction "K2_P$3") (pintype "bidirectional"))
      (node (ref "RN5") (pin "3") (pinfunction "1_3") (pintype "passive"))
    )
    (net (code "26") (name "Net-(B8-SW2)") (class "Default")
      (node (ref "B8") (pin "P$5") (pinfunction "SW2_P$5") (pintype "bidirectional"))
      (node (ref "B8ALT") (pin "P$5") (pinfunction "SW2_P$5") (pintype "bidirectional"))
      (node (ref "IC1") (pin "21") (pinfunction "GPA0_21") (pintype "bidirectional"))
    )
    (net (code "27") (name "Net-(B9-K1)") (class "Default")
      (node (ref "B9") (pin "P$2") (pinfunction "K1_P$2") (pintype "bidirectional"))
      (node (ref "RN7") (pin "1") (pinfunction "1_1") (pintype "passive"))
    )
    (net (code "28") (name "Net-(B9-K2)") (class "Default")
      (node (ref "B9") (pin "P$3") (pinfunction "K2_P$3") (pintype "bidirectional"))
      (node (ref "RN7") (pin "3") (pinfunction "1_3") (pintype "passive"))
    )
    (net (code "29") (name "Net-(B9-SW2)") (class "Default")
      (node (ref "B9") (pin "P$5") (pinfunction "SW2_P$5") (pintype "bidirectional"))
      (node (ref "IC4") (pin "25") (pinfunction "GPA4_25") (pintype "bidirectional"))
    )
    (net (code "30") (name "Net-(B10-K1)") (class "Default")
      (node (ref "B10") (pin "P$2") (pinfunction "K1_P$2") (pintype "bidirectional"))
      (node (ref "RN7") (pin "5") (pinfunction "1_5") (pintype "passive"))
    )
    (net (code "31") (name "Net-(B10-K2)") (class "Default")
      (node (ref "B10") (pin "P$3") (pinfunction "K2_P$3") (pintype "bidirectional"))
      (node (ref "RN7") (pin "7") (pinfunction "1_7") (pintype "passive"))
    )
    (net (code "32") (name "Net-(B10-SW2)") (class "Default")
      (node (ref "B10") (pin "P$5") (pinfunction "SW2_P$5") (pintype "bidirectional"))
      (node (ref "IC4") (pin "26") (pinfunction "GPA5_26") (pintype "bidirectional"))
    )
    (net (code "33") (name "Net-(B11-K1)") (class "Default")
      (node (ref "B11") (pin "P$2") (pinfunction "K1_P$2") (pintype "bidirectional"))
      (node (ref "RN8") (pin "1") (pinfunction "1_1") (pintype "passive"))
    )
    (net (code "34") (name "Net-(B11-K2)") (class "Default")
      (node (ref "B11") (pin "P$3") (pinfunction "K2_P$3") (pintype "bidirectional"))
      (node (ref "RN8") (pin "3") (pinfunction "1_3") (pintype "passive"))
    )
    (net (code "35") (name "Net-(B11-SW2)") (class "Default")
      (node (ref "B11") (pin "P$5") (pinfunction "SW2_P$5") (pintype "bidirectional"))
      (node (ref "IC4") (pin "27") (pinfunction "GPA6_27") (pintype "bidirectional"))
    )
    (net (code "36") (name "Net-(B12-K1)") (class "Default")
      (node (ref "B12") (pin "P$2") (pinfunction "K1_P$2") (pintype "bidirectional"))
      (node (ref "RN8") (pin "5") (pinfunction "1_5") (pintype "passive"))
    )
    (net (code "37") (name "Net-(B12-K2)") (class "Default")
      (node (ref "B12") (pin "P$3") (pinfunction "K2_P$3") (pintype "bidirectional"))
      (node (ref "RN8") (pin "7") (pinfunction "1_7") (pintype "passive"))
    )
    (net (code "38") (name "Net-(B12-SW2)") (class "Default")
      (node (ref "B12") (pin "P$5") (pinfunction "SW2_P$5") (pintype "bidirectional"))
      (node (ref "IC4") (pin "28") (pinfunction "GPA7_28") (pintype "bidirectional"))
    )
    (net (code "39") (name "Net-(B13-K1)") (class "Default")
      (node (ref "B13") (pin "P$2") (pinfunction "K1_P$2") (pintype "bidirectional"))
      (node (ref "RN10") (pin "5") (pinfunction "1_5") (pintype "passive"))
    )
    (net (code "40") (name "Net-(B13-K2)") (class "Default")
      (node (ref "B13") (pin "P$3") (pinfunction "K2_P$3") (pintype "bidirectional"))
      (node (ref "RN10") (pin "7") (pinfunction "1_7") (pintype "passive"))
    )
    (net (code "41") (name "Net-(B13-SW2)") (class "Default")
      (node (ref "B13") (pin "P$5") (pinfunction "SW2_P$5") (pintype "bidirectional"))
      (node (ref "IC4") (pin "24") (pinfunction "GPA3_24") (pintype "bidirectional"))
    )
    (net (code "42") (name "Net-(B14-K1)") (class "Default")
      (node (ref "B14") (pin "P$2") (pinfunction "K1_P$2") (pintype "bidirectional"))
      (node (ref "RN10") (pin "1") (pinfunction "1_1") (pintype "passive"))
    )
    (net (code "43") (name "Net-(B14-K2)") (class "Default")
      (node (ref "B14") (pin "P$3") (pinfunction "K2_P$3") (pintype "bidirectional"))
      (node (ref "RN10") (pin "3") (pinfunction "1_3") (pintype "passive"))
    )
    (net (code "44") (name "Net-(B14-SW2)") (class "Default")
      (node (ref "B14") (pin "P$5") (pinfunction "SW2_P$5") (pintype "bidirectional"))
      (node (ref "IC4") (pin "23") (pinfunction "GPA2_23") (pintype "bidirectional"))
    )
    (net (code "45") (name "Net-(B15-K1)") (class "Default")
      (node (ref "B15") (pin "P$2") (pinfunction "K1_P$2") (pintype "bidirectional"))
      (node (ref "B15ALT") (pin "P$2") (pinfunction "K1_P$2") (pintype "bidirectional"))
      (node (ref "RN9") (pin "5") (pinfunction "1_5") (pintype "passive"))
    )
    (net (code "46") (name "Net-(B15-K2)") (class "Default")
      (node (ref "B15") (pin "P$3") (pinfunction "K2_P$3") (pintype "bidirectional"))
      (node (ref "B15ALT") (pin "P$3") (pinfunction "K2_P$3") (pintype "bidirectional"))
      (node (ref "RN9") (pin "7") (pinfunction "1_7") (pintype "passive"))
    )
    (net (code "47") (name "Net-(B15-SW2)") (class "Default")
      (node (ref "B15") (pin "P$5") (pinfunction "SW2_P$5") (pintype "bidirectional"))
      (node (ref "B15ALT") (pin "P$5") (pinfunction "SW2_P$5") (pintype "bidirectional"))
      (node (ref "IC4") (pin "22") (pinfunction "GPA1_22") (pintype "bidirectional"))
    )
    (net (code "48") (name "Net-(B16-K1)") (class "Default")
      (node (ref "B16") (pin "P$2") (pinfunction "K1_P$2") (pintype "bidirectional"))
      (node (ref "B16ALT") (pin "P$2") (pinfunction "K1_P$2") (pintype "bidirectional"))
      (node (ref "RN9") (pin "1") (pinfunction "1_1") (pintype "passive"))
    )
    (net (code "49") (name "Net-(B16-K2)") (class "Default")
      (node (ref "B16") (pin "P$3") (pinfunction "K2_P$3") (pintype "bidirectional"))
      (node (ref "B16ALT") (pin "P$3") (pinfunction "K2_P$3") (pintype "bidirectional"))
      (node (ref "RN9") (pin "3") (pinfunction "1_3") (pintype "passive"))
    )
    (net (code "50") (name "Net-(B16-SW2)") (class "Default")
      (node (ref "B16") (pin "P$5") (pinfunction "SW2_P$5") (pintype "bidirectional"))
      (node (ref "B16ALT") (pin "P$5") (pinfunction "SW2_P$5") (pintype "bidirectional"))
      (node (ref "IC4") (pin "21") (pinfunction "GPA0_21") (pintype "bidirectional"))
    )
    (net (code "51") (name "Net-(B17-K1)") (class "Default")
      (node (ref "B17") (pin "P$2") (pinfunction "K1_P$2") (pintype "bidirectional"))
      (node (ref "RN11") (pin "1") (pinfunction "1_1") (pintype "passive"))
    )
    (net (code "52") (name "Net-(B17-K2)") (class "Default")
      (node (ref "B17") (pin "P$3") (pinfunction "K2_P$3") (pintype "bidirectional"))
      (node (ref "RN11") (pin "3") (pinfunction "1_3") (pintype "passive"))
    )
    (net (code "53") (name "Net-(B17-SW2)") (class "Default")
      (node (ref "B17") (pin "P$5") (pinfunction "SW2_P$5") (pintype "bidirectional"))
      (node (ref "IC6") (pin "25") (pinfunction "GPA4_25") (pintype "bidirectional"))
    )
    (net (code "54") (name "Net-(B18-K1)") (class "Default")
      (node (ref "B18") (pin "P$2") (pinfunction "K1_P$2") (pintype "bidirectional"))
      (node (ref "RN11") (pin "5") (pinfunction "1_5") (pintype "passive"))
    )
    (net (code "55") (name "Net-(B18-K2)") (class "Default")
      (node (ref "B18") (pin "P$3") (pinfunction "K2_P$3") (pintype "bidirectional"))
      (node (ref "RN11") (pin "7") (pinfunction "1_7") (pintype "passive"))
    )
    (net (code "56") (name "Net-(B18-SW2)") (class "Default")
      (node (ref "B18") (pin "P$5") (pinfunction "SW2_P$5") (pintype "bidirectional"))
      (node (ref "IC6") (pin "26") (pinfunction "GPA5_26") (pintype "bidirectional"))
    )
    (net (code "57") (name "Net-(B19-K1)") (class "Default")
      (node (ref "B19") (pin "P$2") (pinfunction "K1_P$2") (pintype "bidirectional"))
      (node (ref "RN12") (pin "1") (pinfunction "1_1") (pintype "passive"))
    )
    (net (code "58") (name "Net-(B19-K2)") (class "Default")
      (node (ref "B19") (pin "P$3") (pinfunction "K2_P$3") (pintype "bidirectional"))
      (node (ref "RN12") (pin "3") (pinfunction "1_3") (pintype "passive"))
    )
    (net (code "59") (name "Net-(B19-SW2)") (class "Default")
      (node (ref "B19") (pin "P$5") (pinfunction "SW2_P$5") (pintype "bidirectional"))
      (node (ref "IC6") (pin "27") (pinfunction "GPA6_27") (pintype "bidirectional"))
    )
    (net (code "60") (name "Net-(B20-K1)") (class "Default")
      (node (ref "B20") (pin "P$2") (pinfunction "K1_P$2") (pintype "bidirectional"))
      (node (ref "RN12") (pin "5") (pinfunction "1_5") (pintype "passive"))
    )
    (net (code "61") (name "Net-(B20-K2)") (class "Default")
      (node (ref "B20") (pin "P$3") (pinfunction "K2_P$3") (pintype "bidirectional"))
      (node (ref "RN12") (pin "7") (pinfunction "1_7") (pintype "passive"))
    )
    (net (code "62") (name "Net-(B20-SW2)") (class "Default")
      (node (ref "B20") (pin "P$5") (pinfunction "SW2_P$5") (pintype "bidirectional"))
      (node (ref "IC6") (pin "28") (pinfunction "GPA7_28") (pintype "bidirectional"))
    )
    (net (code "63") (name "Net-(B21-K1)") (class "Default")
      (node (ref "B21") (pin "P$2") (pinfunction "K1_P$2") (pintype "bidirectional"))
      (node (ref "RN14") (pin "5") (pinfunction "1_5") (pintype "passive"))
    )
    (net (code "64") (name "Net-(B21-K2)") (class "Default")
      (node (ref "B21") (pin "P$3") (pinfunction "K2_P$3") (pintype "bidirectional"))
      (node (ref "RN14") (pin "7") (pinfunction "1_7") (pintype "passive"))
    )
    (net (code "65") (name "Net-(B21-SW2)") (class "Default")
      (node (ref "B21") (pin "P$5") (pinfunction "SW2_P$5") (pintype "bidirectional"))
      (node (ref "IC6") (pin "24") (pinfunction "GPA3_24") (pintype "bidirectional"))
    )
    (net (code "66") (name "Net-(B22-K1)") (class "Default")
      (node (ref "B22") (pin "P$2") (pinfunction "K1_P$2") (pintype "bidirectional"))
      (node (ref "RN14") (pin "1") (pinfunction "1_1") (pintype "passive"))
    )
    (net (code "67") (name "Net-(B22-K2)") (class "Default")
      (node (ref "B22") (pin "P$3") (pinfunction "K2_P$3") (pintype "bidirectional"))
      (node (ref "RN14") (pin "3") (pinfunction "1_3") (pintype "passive"))
    )
    (net (code "68") (name "Net-(B22-SW2)") (class "Default")
      (node (ref "B22") (pin "P$5") (pinfunction "SW2_P$5") (pintype "bidirectional"))
      (node (ref "IC6") (pin "23") (pinfunction "GPA2_23") (pintype "bidirectional"))
    )
    (net (code "69") (name "Net-(B23-K1)") (class "Default")
      (node (ref "B23") (pin "P$2") (pinfunction "K1_P$2") (pintype "bidirectional"))
      (node (ref "B23ALT") (pin "P$2") (pinfunction "K1_P$2") (pintype "bidirectional"))
      (node (ref "RN13") (pin "5") (pinfunction "1_5") (pintype "passive"))
    )
    (net (code "70") (name "Net-(B23-K2)") (class "Default")
      (node (ref "B23") (pin "P$3") (pinfunction "K2_P$3") (pintype "bidirectional"))
      (node (ref "B23ALT") (pin "P$3") (pinfunction "K2_P$3") (pintype "bidirectional"))
      (node (ref "RN13") (pin "7") (pinfunction "1_7") (pintype "passive"))
    )
    (net (code "71") (name "Net-(B23-SW2)") (class "Default")
      (node (ref "B23") (pin "P$5") (pinfunction "SW2_P$5") (pintype "bidirectional"))
      (node (ref "B23ALT") (pin "P$5") (pinfunction "SW2_P$5") (pintype "bidirectional"))
      (node (ref "IC6") (pin "22") (pinfunction "GPA1_22") (pintype "bidirectional"))
    )
    (net (code "72") (name "Net-(B24-K1)") (class "Default")
      (node (ref "B24") (pin "P$2") (pinfunction "K1_P$2") (pintype "bidirectional"))
      (node (ref "B24ALT") (pin "P$2") (pinfunction "K1_P$2") (pintype "bidirectional"))
      (node (ref "RN13") (pin "1") (pinfunction "1_1") (pintype "passive"))
    )
    (net (code "73") (name "Net-(B24-K2)") (class "Default")
      (node (ref "B24") (pin "P$3") (pinfunction "K2_P$3") (pintype "bidirectional"))
      (node (ref "B24ALT") (pin "P$3") (pinfunction "K2_P$3") (pintype "bidirectional"))
      (node (ref "RN13") (pin "3") (pinfunction "1_3") (pintype "passive"))
    )
    (net (code "74") (name "Net-(B24-SW2)") (class "Default")
      (node (ref "B24") (pin "P$5") (pinfunction "SW2_P$5") (pintype "bidirectional"))
      (node (ref "B24ALT") (pin "P$5") (pinfunction "SW2_P$5") (pintype "bidirectional"))
      (node (ref "IC6") (pin "21") (pinfunction "GPA0_21") (pintype "bidirectional"))
    )
    (net (code "75") (name "Net-(IC1-SCL)") (class "Default")
      (node (ref "IC1") (pin "12") (pinfunction "SCL_12") (pintype "input"))
      (node (ref "IC2") (pin "26") (pinfunction "SCL_26") (pintype "input"))
      (node (ref "IC3") (pin "26") (pinfunction "SCL_26") (pintype "input"))
      (node (ref "IC4") (pin "12") (pinfunction "SCL_12") (pintype "input"))
      (node (ref "IC5") (pin "26") (pinfunction "SCL_26") (pintype "input"))
      (node (ref "IC6") (pin "12") (pinfunction "SCL_12") (pintype "input"))
      (node (ref "R2") (pin "1") (pinfunction "1_1") (pintype "passive"))
      (node (ref "U1") (pin "A5") (pinfunction "A5_A5") (pintype "bidirectional"))
    )
    (net (code "76") (name "Net-(IC1-SDA)") (class "Default")
      (node (ref "IC1") (pin "13") (pinfunction "SDA_13") (pintype "bidirectional"))
      (node (ref "IC2") (pin "27") (pinfunction "SDA_27") (pintype "input"))
      (node (ref "IC3") (pin "27") (pinfunction "SDA_27") (pintype "input"))
      (node (ref "IC4") (pin "13") (pinfunction "SDA_13") (pintype "bidirectional"))
      (node (ref "IC5") (pin "27") (pinfunction "SDA_27") (pintype "input"))
      (node (ref "IC6") (pin "13") (pinfunction "SDA_13") (pintype "bidirectional"))
      (node (ref "R1") (pin "1") (pinfunction "1_1") (pintype "passive"))
      (node (ref "U1") (pin "A4") (pinfunction "A4_A4") (pintype "bidirectional"))
    )
    (net (code "77") (name "Net-(IC2-L0)") (class "Default")
      (node (ref "IC2") (pin "6") (pinfunction "L0_6") (pintype "output"))
      (node (ref "RN3") (pin "2") (pinfunction "2_2") (pintype "passive"))
    )
    (net (code "78") (name "Net-(IC2-L1)") (class "Default")
      (node (ref "IC2") (pin "7") (pinfunction "L1_7") (pintype "output"))
      (node (ref "RN3") (pin "4") (pinfunction "2_4") (pintype "passive"))
    )
    (net (code "79") (name "Net-(IC2-L2)") (class "Default")
      (node (ref "IC2") (pin "8") (pinfunction "L2_8") (pintype "output"))
      (node (ref "RN3") (pin "6") (pinfunction "2_6") (pintype "passive"))
    )
    (net (code "80") (name "Net-(IC2-L3)") (class "Default")
      (node (ref "IC2") (pin "9") (pinfunction "L3_9") (pintype "output"))
      (node (ref "RN3") (pin "8") (pinfunction "2_8") (pintype "passive"))
    )
    (net (code "81") (name "Net-(IC2-L4)") (class "Default")
      (node (ref "IC2") (pin "10") (pinfunction "L4_10") (pintype "output"))
      (node (ref "RN4") (pin "2") (pinfunction "2_2") (pintype "passive"))
    )
    (net (code "82") (name "Net-(IC2-L5)") (class "Default")
      (node (ref "IC2") (pin "11") (pinfunction "L5_11") (pintype "output"))
      (node (ref "RN4") (pin "4") (pinfunction "2_4") (pintype "passive"))
    )
    (net (code "83") (name "Net-(IC2-L6)") (class "Default")
      (node (ref "IC2") (pin "12") (pinfunction "L6_12") (pintype "output"))
      (node (ref "RN4") (pin "6") (pinfunction "2_6") (pintype "passive"))
    )
    (net (code "84") (name "Net-(IC2-L7)") (class "Default")
      (node (ref "IC2") (pin "13") (pinfunction "L7_13") (pintype "output"))
      (node (ref "RN4") (pin "8") (pinfunction "2_8") (pintype "passive"))
    )
    (net (code "85") (name "Net-(IC2-L8)") (class "Default")
      (node (ref "IC2") (pin "15") (pinfunction "L8_15") (pintype "output"))
      (node (ref "RN6") (pin "8") (pinfunction "2_8") (pintype "passive"))
    )
    (net (code "86") (name "Net-(IC2-L9)") (class "Default")
      (node (ref "IC2") (pin "16") (pinfunction "L9_16") (pintype "output"))
      (node (ref "RN6") (pin "6") (pinfunction "2_6") (pintype "passive"))
    )
    (net (code "87") (name "Net-(IC2-L10)") (class "Default")
      (node (ref "IC2") (pin "17") (pinfunction "L10_17") (pintype "output"))
      (node (ref "RN6") (pin "4") (pinfunction "2_4") (pintype "passive"))
    )
    (net (code "88") (name "Net-(IC2-L11)") (class "Default")
      (node (ref "IC2") (pin "18") (pinfunction "L11_18") (pintype "output"))
      (node (ref "RN6") (pin "2") (pinfunction "2_2") (pintype "passive"))
    )
    (net (code "89") (name "Net-(IC2-L12)") (class "Default")
      (node (ref "IC2") (pin "19") (pinfunction "L12_19") (pintype "output"))
      (node (ref "RN5") (pin "8") (pinfunction "2_8") (pintype "passive"))
    )
    (net (code "90") (name "Net-(IC2-L13)") (class "Default")
      (node (ref "IC2") (pin "20") (pinfunction "L13_20") (pintype "output"))
      (node (ref "RN5") (pin "6") (pinfunction "2_6") (pintype "passive"))
    )
    (net (code "91") (name "Net-(IC2-L14)") (class "Default")
      (node (ref "IC2") (pin "21") (pinfunction "L14_21") (pintype "output"))
      (node (ref "RN5") (pin "4") (pinfunction "2_4") (pintype "passive"))
    )
    (net (code "92") (name "Net-(IC2-L15)") (class "Default")
      (node (ref "IC2") (pin "22") (pinfunction "L15_22") (pintype "output"))
      (node (ref "RN5") (pin "2") (pinfunction "2_2") (pintype "passive"))
    )
    (net (code "93") (name "Net-(IC3-L0)") (class "Default")
      (node (ref "IC3") (pin "6") (pinfunction "L0_6") (pintype "output"))
      (node (ref "RN7") (pin "2") (pinfunction "2_2") (pintype "passive"))
    )
    (net (code "94") (name "Net-(IC3-L1)") (class "Default")
      (node (ref "IC3") (pin "7") (pinfunction "L1_7") (pintype "output"))
      (node (ref "RN7") (pin "4") (pinfunction "2_4") (pintype "passive"))
    )
    (net (code "95") (name "Net-(IC3-L2)") (class "Default")
      (node (ref "IC3") (pin "8") (pinfunction "L2_8") (pintype "output"))
      (node (ref "RN7") (pin "6") (pinfunction "2_6") (pintype "passive"))
    )
    (net (code "96") (name "Net-(IC3-L3)") (class "Default")
      (node (ref "IC3") (pin "9") (pinfunction "L3_9") (pintype "output"))
      (node (ref "RN7") (pin "8") (pinfunction "2_8") (pintype "passive"))
    )
    (net (code "97") (name "Net-(IC3-L4)") (class "Default")
      (node (ref "IC3") (pin "10") (pinfunction "L4_10") (pintype "output"))
      (node (ref "RN8") (pin "2") (pinfunction "2_2") (pintype "passive"))
    )
    (net (code "98") (name "Net-(IC3-L5)") (class "Default")
      (node (ref "IC3") (pin "11") (pinfunction "L5_11") (pintype "output"))
      (node (ref "RN8") (pin "4") (pinfunction "2_4") (pintype "passive"))
    )
    (net (code "99") (name "Net-(IC3-L6)") (class "Default")
      (node (ref "IC3") (pin "12") (pinfunction "L6_12") (pintype "output"))
      (node (ref "RN8") (pin "6") (pinfunction "2_6") (pintype "passive"))
    )
    (net (code "100") (name "Net-(IC3-L7)") (class "Default")
      (node (ref "IC3") (pin "13") (pinfunction "L7_13") (pintype "output"))
      (node (ref "RN8") (pin "8") (pinfunction "2_8") (pintype "passive"))
    )
    (net (code "101") (name "Net-(IC3-L8)") (class "Default")
      (node (ref "IC3") (pin "15") (pinfunction "L8_15") (pintype "output"))
      (node (ref "RN10") (pin "8") (pinfunction "2_8") (pintype "passive"))
    )
    (net (code "102") (name "Net-(IC3-L9)") (class "Default")
      (node (ref "IC3") (pin "16") (pinfunction "L9_16") (pintype "output"))
      (node (ref "RN10") (pin "6") (pinfunction "2_6") (pintype "passive"))
    )
    (net (code "103") (name "Net-(IC3-L10)") (class "Default")
      (node (ref "IC3") (pin "17") (pinfunction "L10_17") (pintype "output"))
      (node (ref "RN10") (pin "4") (pinfunction "2_4") (pintype "passive"))
    )
    (net (code "104") (name "Net-(IC3-L11)") (class "Default")
      (node (ref "IC3") (pin "18") (pinfunction "L11_18") (pintype "output"))
      (node (ref "RN10") (pin "2") (pinfunction "2_2") (pintype "passive"))
    )
    (net (code "105") (name "Net-(IC3-L12)") (class "Default")
      (node (ref "IC3") (pin "19") (pinfunction "L12_19") (pintype "output"))
      (node (ref "RN9") (pin "8") (pinfunction "2_8") (pintype "passive"))
    )
    (net (code "106") (name "Net-(IC3-L13)") (class "Default")
      (node (ref "IC3") (pin "20") (pinfunction "L13_20") (pintype "output"))
      (node (ref "RN9") (pin "6") (pinfunction "2_6") (pintype "passive"))
    )
    (net (code "107") (name "Net-(IC3-L14)") (class "Default")
      (node (ref "IC3") (pin "21") (pinfunction "L14_21") (pintype "output"))
      (node (ref "RN9") (pin "4") (pinfunction "2_4") (pintype "passive"))
    )
    (net (code "108") (name "Net-(IC3-L15)") (class "Default")
      (node (ref "IC3") (pin "22") (pinfunction "L15_22") (pintype "output"))
      (node (ref "RN9") (pin "2") (pinfunction "2_2") (pintype "passive"))
    )
    (net (code "109") (name "Net-(IC5-L0)") (class "Default")
      (node (ref "IC5") (pin "6") (pinfunction "L0_6") (pintype "output"))
      (node (ref "RN11") (pin "2") (pinfunction "2_2") (pintype "passive"))
    )
    (net (code "110") (name "Net-(IC5-L1)") (class "Default")
      (node (ref "IC5") (pin "7") (pinfunction "L1_7") (pintype "output"))
      (node (ref "RN11") (pin "4") (pinfunction "2_4") (pintype "passive"))
    )
    (net (code "111") (name "Net-(IC5-L2)") (class "Default")
      (node (ref "IC5") (pin "8") (pinfunction "L2_8") (pintype "output"))
      (node (ref "RN11") (pin "6") (pinfunction "2_6") (pintype "passive"))
    )
    (net (code "112") (name "Net-(IC5-L3)") (class "Default")
      (node (ref "IC5") (pin "9") (pinfunction "L3_9") (pintype "output"))
      (node (ref "RN11") (pin "8") (pinfunction "2_8") (pintype "passive"))
    )
    (net (code "113") (name "Net-(IC5-L4)") (class "Default")
      (node (ref "IC5") (pin "10") (pinfunction "L4_10") (pintype "output"))
      (node (ref "RN12") (pin "2") (pinfunction "2_2") (pintype "passive"))
    )
    (net (code "114") (name "Net-(IC5-L5)") (class "Default")
      (node (ref "IC5") (pin "11") (pinfunction "L5_11") (pintype "output"))
      (node (ref "RN12") (pin "4") (pinfunction "2_4") (pintype "passive"))
    )
    (net (code "115") (name "Net-(IC5-L6)") (class "Default")
      (node (ref "IC5") (pin "12") (pinfunction "L6_12") (pintype "output"))
      (node (ref "RN12") (pin "6") (pinfunction "2_6") (pintype "passive"))
    )
    (net (code "116") (name "Net-(IC5-L7)") (class "Default")
      (node (ref "IC5") (pin "13") (pinfunction "L7_13") (pintype "output"))
      (node (ref "RN12") (pin "8") (pinfunction "2_8") (pintype "passive"))
    )
    (net (code "117") (name "Net-(IC5-L8)") (class "Default")
      (node (ref "IC5") (pin "15") (pinfunction "L8_15") (pintype "output"))
      (node (ref "RN14") (pin "8") (pinfunction "2_8") (pintype "passive"))
    )
    (net (code "118") (name "Net-(IC5-L9)") (class "Default")
      (node (ref "IC5") (pin "16") (pinfunction "L9_16") (pintype "output"))
      (node (ref "RN14") (pin "6") (pinfunction "2_6") (pintype "passive"))
    )
    (net (code "119") (name "Net-(IC5-L10)") (class "Default")
      (node (ref "IC5") (pin "17") (pinfunction "L10_17") (pintype "output"))
      (node (ref "RN14") (pin "4") (pinfunction "2_4") (pintype "passive"))
    )
    (net (code "120") (name "Net-(IC5-L11)") (class "Default")
      (node (ref "IC5") (pin "18") (pinfunction "L11_18") (pintype "output"))
      (node (ref "RN14") (pin "2") (pinfunction "2_2") (pintype "passive"))
    )
    (net (code "121") (name "Net-(IC5-L12)") (class "Default")
      (node (ref "IC5") (pin "19") (pinfunction "L12_19") (pintype "output"))
      (node (ref "RN13") (pin "8") (pinfunction "2_8") (pintype "passive"))
    )
    (net (code "122") (name "Net-(IC5-L13)") (class "Default")
      (node (ref "IC5") (pin "20") (pinfunction "L13_20") (pintype "output"))
      (node (ref "RN13") (pin "6") (pinfunction "2_6") (pintype "passive"))
    )
    (net (code "123") (name "Net-(IC5-L14)") (class "Default")
      (node (ref "IC5") (pin "21") (pinfunction "L14_21") (pintype "output"))
      (node (ref "RN13") (pin "4") (pinfunction "2_4") (pintype "passive"))
    )
    (net (code "124") (name "Net-(IC5-L15)") (class "Default")
      (node (ref "IC5") (pin "22") (pinfunction "L15_22") (pintype "output"))
      (node (ref "RN13") (pin "2") (pinfunction "2_2") (pintype "passive"))
    )
    (net (code "125") (name "Net-(JP2-Pad2)") (class "Default")
      (node (ref "JP2") (pin "2") (pinfunction "2_2") (pintype "passive"))
      (node (ref "RN15") (pin "2") (pinfunction "2_2") (pintype "passive"))
      (node (ref "SW2") (pin "B") (pinfunction "B_B") (pintype "passive"))
      (node (ref "U1") (pin "D7") (pinfunction "D7_D7") (pintype "bidirectional"))
    )
    (net (code "126") (name "Net-(JP7-Pad3)") (class "Default")
      (node (ref "JP7") (pin "3") (pinfunction "3_3") (pintype "passive"))
      (node (ref "U1") (pin "D2") (pinfunction "D2_D2") (pintype "bidirectional"))
    )
    (net (code "127") (name "Net-(RN1B-2)") (class "Default")
      (node (ref "JP1") (pin "4") (pinfunction "4_4") (pintype "passive"))
      (node (ref "RN1") (pin "4") (pinfunction "2_4") (pintype "passive"))
      (node (ref "SW1") (pin "A") (pinfunction "A_A") (pintype "passive"))
      (node (ref "U1") (pin "D5") (pinfunction "*D5_D5") (pintype "bidirectional"))
    )
    (net (code "128") (name "Net-(RN1C-2)") (class "Default")
      (node (ref "JP2") (pin "1") (pinfunction "1_1") (pintype "passive"))
      (node (ref "RN1") (pin "6") (pinfunction "2_6") (pintype "passive"))
      (node (ref "SW1") (pin "E") (pinfunction "2_E") (pintype "passive"))
      (node (ref "U1") (pin "D6") (pinfunction "*D6_D6") (pintype "bidirectional"))
    )
    (net (code "129") (name "Net-(RN15B-2)") (class "Default")
      (node (ref "JP2") (pin "3") (pinfunction "3_3") (pintype "passive"))
      (node (ref "RN15") (pin "4") (pinfunction "2_4") (pintype "passive"))
      (node (ref "SW2") (pin "A") (pinfunction "A_A") (pintype "passive"))
      (node (ref "U1") (pin "D8") (pinfunction "D8_D8") (pintype "bidirectional"))
    )
    (net (code "130") (name "Net-(RN15C-2)") (class "Default")
      (node (ref "JP2") (pin "4") (pinfunction "4_4") (pintype "passive"))
      (node (ref "RN15") (pin "6") (pinfunction "2_6") (pintype "passive"))
      (node (ref "SW2") (pin "E") (pinfunction "2_E") (pintype "passive"))
      (node (ref "U1") (pin "D9") (pinfunction "*D9_D9") (pintype "bidirectional"))
    )
    (net (code "131") (name "Net-(U$22-S)") (class "Default")
      (node (ref "JP3") (pin "3") (pinfunction "3_3") (pintype "passive"))
      (node (ref "U$22") (pin "2A") (pinfunction "S_2A") (pintype "passive"))
      (node (ref "U1") (pin "A0") (pinfunction "A0_A0") (pintype "bidirectional"))
    )
    (net (code "132") (name "Net-(U1-*D3)") (class "Default")
      (node (ref "JP1") (pin "3") (pinfunction "3_3") (pintype "passive"))
      (node (ref "RN1") (pin "2") (pinfunction "2_2") (pintype "passive"))
      (node (ref "SW1") (pin "B") (pinfunction "B_B") (pintype "passive"))
      (node (ref "U1") (pin "D3") (pinfunction "*D3_D3") (pintype "bidirectional"))
    )
    (net (code "133") (name "unconnected-(IC1-GPB0-Pad1)") (class "Default")
      (node (ref "IC1") (pin "1") (pinfunction "GPB0_1") (pintype "bidirectional"))
    )
    (net (code "134") (name "unconnected-(IC1-GPB1-Pad2)") (class "Default")
      (node (ref "IC1") (pin "2") (pinfunction "GPB1_2") (pintype "bidirectional"))
    )
    (net (code "135") (name "unconnected-(IC1-GPB2-Pad3)") (class "Default")
      (node (ref "IC1") (pin "3") (pinfunction "GPB2_3") (pintype "bidirectional"))
    )
    (net (code "136") (name "unconnected-(IC1-GPB3-Pad4)") (class "Default")
      (node (ref "IC1") (pin "4") (pinfunction "GPB3_4") (pintype "bidirectional"))
    )
    (net (code "137") (name "unconnected-(IC1-GPB4-Pad5)") (class "Default")
      (node (ref "IC1") (pin "5") (pinfunction "GPB4_5") (pintype "bidirectional"))
    )
    (net (code "138") (name "unconnected-(IC1-GPB5-Pad6)") (class "Default")
      (node (ref "IC1") (pin "6") (pinfunction "GPB5_6") (pintype "bidirectional"))
    )
    (net (code "139") (name "unconnected-(IC1-GPB6-Pad7)") (class "Default")
      (node (ref "IC1") (pin "7") (pinfunction "GPB6_7") (pintype "bidirectional"))
    )
    (net (code "140") (name "unconnected-(IC1-GPB7-Pad8)") (class "Default")
      (node (ref "IC1") (pin "8") (pinfunction "GPB7_8") (pintype "bidirectional"))
    )
    (net (code "141") (name "unconnected-(IC1-INTA-Pad20)") (class "Default")
      (node (ref "IC1") (pin "20") (pinfunction "INTA_20") (pintype "output"))
    )
    (net (code "142") (name "unconnected-(IC1-INTB-Pad19)") (class "Default")
      (node (ref "IC1") (pin "19") (pinfunction "INTB_19") (pintype "output"))
    )
    (net (code "143") (name "unconnected-(IC4-GPB0-Pad1)") (class "Default")
      (node (ref "IC4") (pin "1") (pinfunction "GPB0_1") (pintype "bidirectional"))
    )
    (net (code "144") (name "unconnected-(IC4-GPB1-Pad2)") (class "Default")
      (node (ref "IC4") (pin "2") (pinfunction "GPB1_2") (pintype "bidirectional"))
    )
    (net (code "145") (name "unconnected-(IC4-GPB2-Pad3)") (class "Default")
      (node (ref "IC4") (pin "3") (pinfunction "GPB2_3") (pintype "bidirectional"))
    )
    (net (code "146") (name "unconnected-(IC4-GPB3-Pad4)") (class "Default")
      (node (ref "IC4") (pin "4") (pinfunction "GPB3_4") (pintype "bidirectional"))
    )
    (net (code "147") (name "unconnected-(IC4-GPB4-Pad5)") (class "Default")
      (node (ref "IC4") (pin "5") (pinfunction "GPB4_5") (pintype "bidirectional"))
    )
    (net (code "148") (name "unconnected-(IC4-GPB5-Pad6)") (class "Default")
      (node (ref "IC4") (pin "6") (pinfunction "GPB5_6") (pintype "bidirectional"))
    )
    (net (code "149") (name "unconnected-(IC4-GPB6-Pad7)") (class "Default")
      (node (ref "IC4") (pin "7") (pinfunction "GPB6_7") (pintype "bidirectional"))
    )
    (net (code "150") (name "unconnected-(IC4-GPB7-Pad8)") (class "Default")
      (node (ref "IC4") (pin "8") (pinfunction "GPB7_8") (pintype "bidirectional"))
    )
    (net (code "151") (name "unconnected-(IC4-INTA-Pad20)") (class "Default")
      (node (ref "IC4") (pin "20") (pinfunction "INTA_20") (pintype "output"))
    )
    (net (code "152") (name "unconnected-(IC4-INTB-Pad19)") (class "Default")
      (node (ref "IC4") (pin "19") (pinfunction "INTB_19") (pintype "output"))
    )
    (net (code "153") (name "unconnected-(IC6-GPB0-Pad1)") (class "Default")
      (node (ref "IC6") (pin "1") (pinfunction "GPB0_1") (pintype "bidirectional"))
    )
    (net (code "154") (name "unconnected-(IC6-GPB1-Pad2)") (class "Default")
      (node (ref "IC6") (pin "2") (pinfunction "GPB1_2") (pintype "bidirectional"))
    )
    (net (code "155") (name "unconnected-(IC6-GPB2-Pad3)") (class "Default")
      (node (ref "IC6") (pin "3") (pinfunction "GPB2_3") (pintype "bidirectional"))
    )
    (net (code "156") (name "unconnected-(IC6-GPB3-Pad4)") (class "Default")
      (node (ref "IC6") (pin "4") (pinfunction "GPB3_4") (pintype "bidirectional"))
    )
    (net (code "157") (name "unconnected-(IC6-GPB4-Pad5)") (class "Default")
      (node (ref "IC6") (pin "5") (pinfunction "GPB4_5") (pintype "bidirectional"))
    )
    (net (code "158") (name "unconnected-(IC6-GPB5-Pad6)") (class "Default")
      (node (ref "IC6") (pin "6") (pinfunction "GPB5_6") (pintype "bidirectional"))
    )
    (net (code "159") (name "unconnected-(IC6-GPB6-Pad7)") (class "Default")
      (node (ref "IC6") (pin "7") (pinfunction "GPB6_7") (pintype "bidirectional"))
    )
    (net (code "160") (name "unconnected-(IC6-GPB7-Pad8)") (class "Default")
      (node (ref "IC6") (pin "8") (pinfunction "GPB7_8") (pintype "bidirectional"))
    )
    (net (code "161") (name "unconnected-(IC6-INTA-Pad20)") (class "Default")
      (node (ref "IC6") (pin "20") (pinfunction "INTA_20") (pintype "output"))
    )
    (net (code "162") (name "unconnected-(IC6-INTB-Pad19)") (class "Default")
      (node (ref "IC6") (pin "19") (pinfunction "INTB_19") (pintype "output"))
    )
    (net (code "163") (name "unconnected-(JP4-Pad1)") (class "Default")
      (node (ref "JP4") (pin "1") (pinfunction "1_1") (pintype "passive"))
    )
    (net (code "164") (name "unconnected-(JP4-Pad2)") (class "Default")
      (node (ref "JP4") (pin "2") (pinfunction "2_2") (pintype "passive"))
    )
    (net (code "165") (name "unconnected-(JP4-Pad3)") (class "Default")
      (node (ref "JP4") (pin "3") (pinfunction "3_3") (pintype "passive"))
    )
    (net (code "166") (name "unconnected-(JP4-Pad4)") (class "Default")
      (node (ref "JP4") (pin "4") (pinfunction "4_4") (pintype "passive"))
    )
    (net (code "167") (name "unconnected-(JP5-Pad1)") (class "Default")
      (node (ref "JP5") (pin "1") (pinfunction "1_1") (pintype "passive"))
    )
    (net (code "168") (name "unconnected-(JP5-Pad2)") (class "Default")
      (node (ref "JP5") (pin "2") (pinfunction "2_2") (pintype "passive"))
    )
    (net (code "169") (name "unconnected-(JP5-Pad3)") (class "Default")
      (node (ref "JP5") (pin "3") (pinfunction "3_3") (pintype "passive"))
    )
    (net (code "170") (name "unconnected-(JP5-Pad4)") (class "Default")
      (node (ref "JP5") (pin "4") (pinfunction "4_4") (pintype "passive"))
    )
    (net (code "171") (name "unconnected-(JP6-Pad1)") (class "Default")
      (node (ref "JP6") (pin "1") (pinfunction "1_1") (pintype "passive"))
    )
    (net (code "172") (name "unconnected-(JP6-Pad2)") (class "Default")
      (node (ref "JP6") (pin "2") (pinfunction "2_2") (pintype "passive"))
    )
    (net (code "173") (name "unconnected-(JP6-Pad3)") (class "Default")
      (node (ref "JP6") (pin "3") (pinfunction "3_3") (pintype "passive"))
    )
    (net (code "174") (name "unconnected-(JP6-Pad4)") (class "Default")
      (node (ref "JP6") (pin "4") (pinfunction "4_4") (pintype "passive"))
    )
    (net (code "175") (name "unconnected-(RN1D-1-Pad7)") (class "Default")
      (node (ref "RN1") (pin "7") (pinfunction "1_7") (pintype "passive"))
    )
    (net (code "176") (name "unconnected-(RN1D-2-Pad8)") (class "Default")
      (node (ref "RN1") (pin "8") (pinfunction "2_8") (pintype "passive"))
    )
    (net (code "177") (name "unconnected-(RN15D-1-Pad7)") (class "Default")
      (node (ref "RN15") (pin "7") (pinfunction "1_7") (pintype "passive"))
    )
    (net (code "178") (name "unconnected-(RN15D-2-Pad8)") (class "Default")
      (node (ref "RN15") (pin "8") (pinfunction "2_8") (pintype "passive"))
    )
    (net (code "179") (name "unconnected-(U1-*D10-PadD10)") (class "Default")
      (node (ref "U1") (pin "D10") (pinfunction "*D10_D10") (pintype "bidirectional"))
    )
    (net (code "180") (name "unconnected-(U1-*D11-PadD11)") (class "Default")
      (node (ref "U1") (pin "D11") (pinfunction "*D11_D11") (pintype "bidirectional"))
    )
    (net (code "181") (name "unconnected-(U1-Pad3.3V)") (class "Default")
      (node (ref "U1") (pin "3.3V") (pinfunction "3.3V_3.3V") (pintype "bidirectional"))
    )
    (net (code "182") (name "unconnected-(U1-PadA1)") (class "Default")
      (node (ref "U1") (pin "A1") (pinfunction "A1_A1") (pintype "bidirectional"))
    )
    (net (code "183") (name "unconnected-(U1-PadA2)") (class "Default")
      (node (ref "U1") (pin "A2") (pinfunction "A2_A2") (pintype "bidirectional"))
    )
    (net (code "184") (name "unconnected-(U1-PadA3)") (class "Default")
      (node (ref "U1") (pin "A3") (pinfunction "A3_A3") (pintype "bidirectional"))
    )
    (net (code "185") (name "unconnected-(U1-PadAREF)") (class "Default")
      (node (ref "U1") (pin "AREF") (pinfunction "AREF_AREF") (pintype "bidirectional"))
    )
    (net (code "186") (name "unconnected-(U1-PadD4)") (class "Default")
      (node (ref "U1") (pin "D4") (pinfunction "D4_D4") (pintype "bidirectional"))
    )
    (net (code "187") (name "unconnected-(U1-PadD12)") (class "Default")
      (node (ref "U1") (pin "D12") (pinfunction "D12_D12") (pintype "bidirectional"))
    )
    (net (code "188") (name "unconnected-(U1-PadD13)") (class "Default")
      (node (ref "U1") (pin "D13") (pinfunction "D13_D13") (pintype "bidirectional"))
    )
    (net (code "189") (name "unconnected-(U1-PadRES)") (class "Default")
      (node (ref "U1") (pin "RES") (pinfunction "RES_RES") (pintype "bidirectional"))
    )
    (net (code "190") (name "unconnected-(U1-PadRX)") (class "Default")
      (node (ref "U1") (pin "RX") (pinfunction "RX_RX") (pintype "bidirectional"))
    )
    (net (code "191") (name "unconnected-(U1-PadTX)") (class "Default")
      (node (ref "U1") (pin "TX") (pinfunction "TX_TX") (pintype "bidirectional"))
    )
    (net (code "192") (name "unconnected-(U1-PadVIN)") (class "Default")
      (node (ref "U1") (pin "VIN") (pinfunction "VIN_VIN") (pintype "bidirectional"))
    )
  )
)
